# PX4FMUv1_6.net
KiCad netlist of a schematic drawn in EAGLE
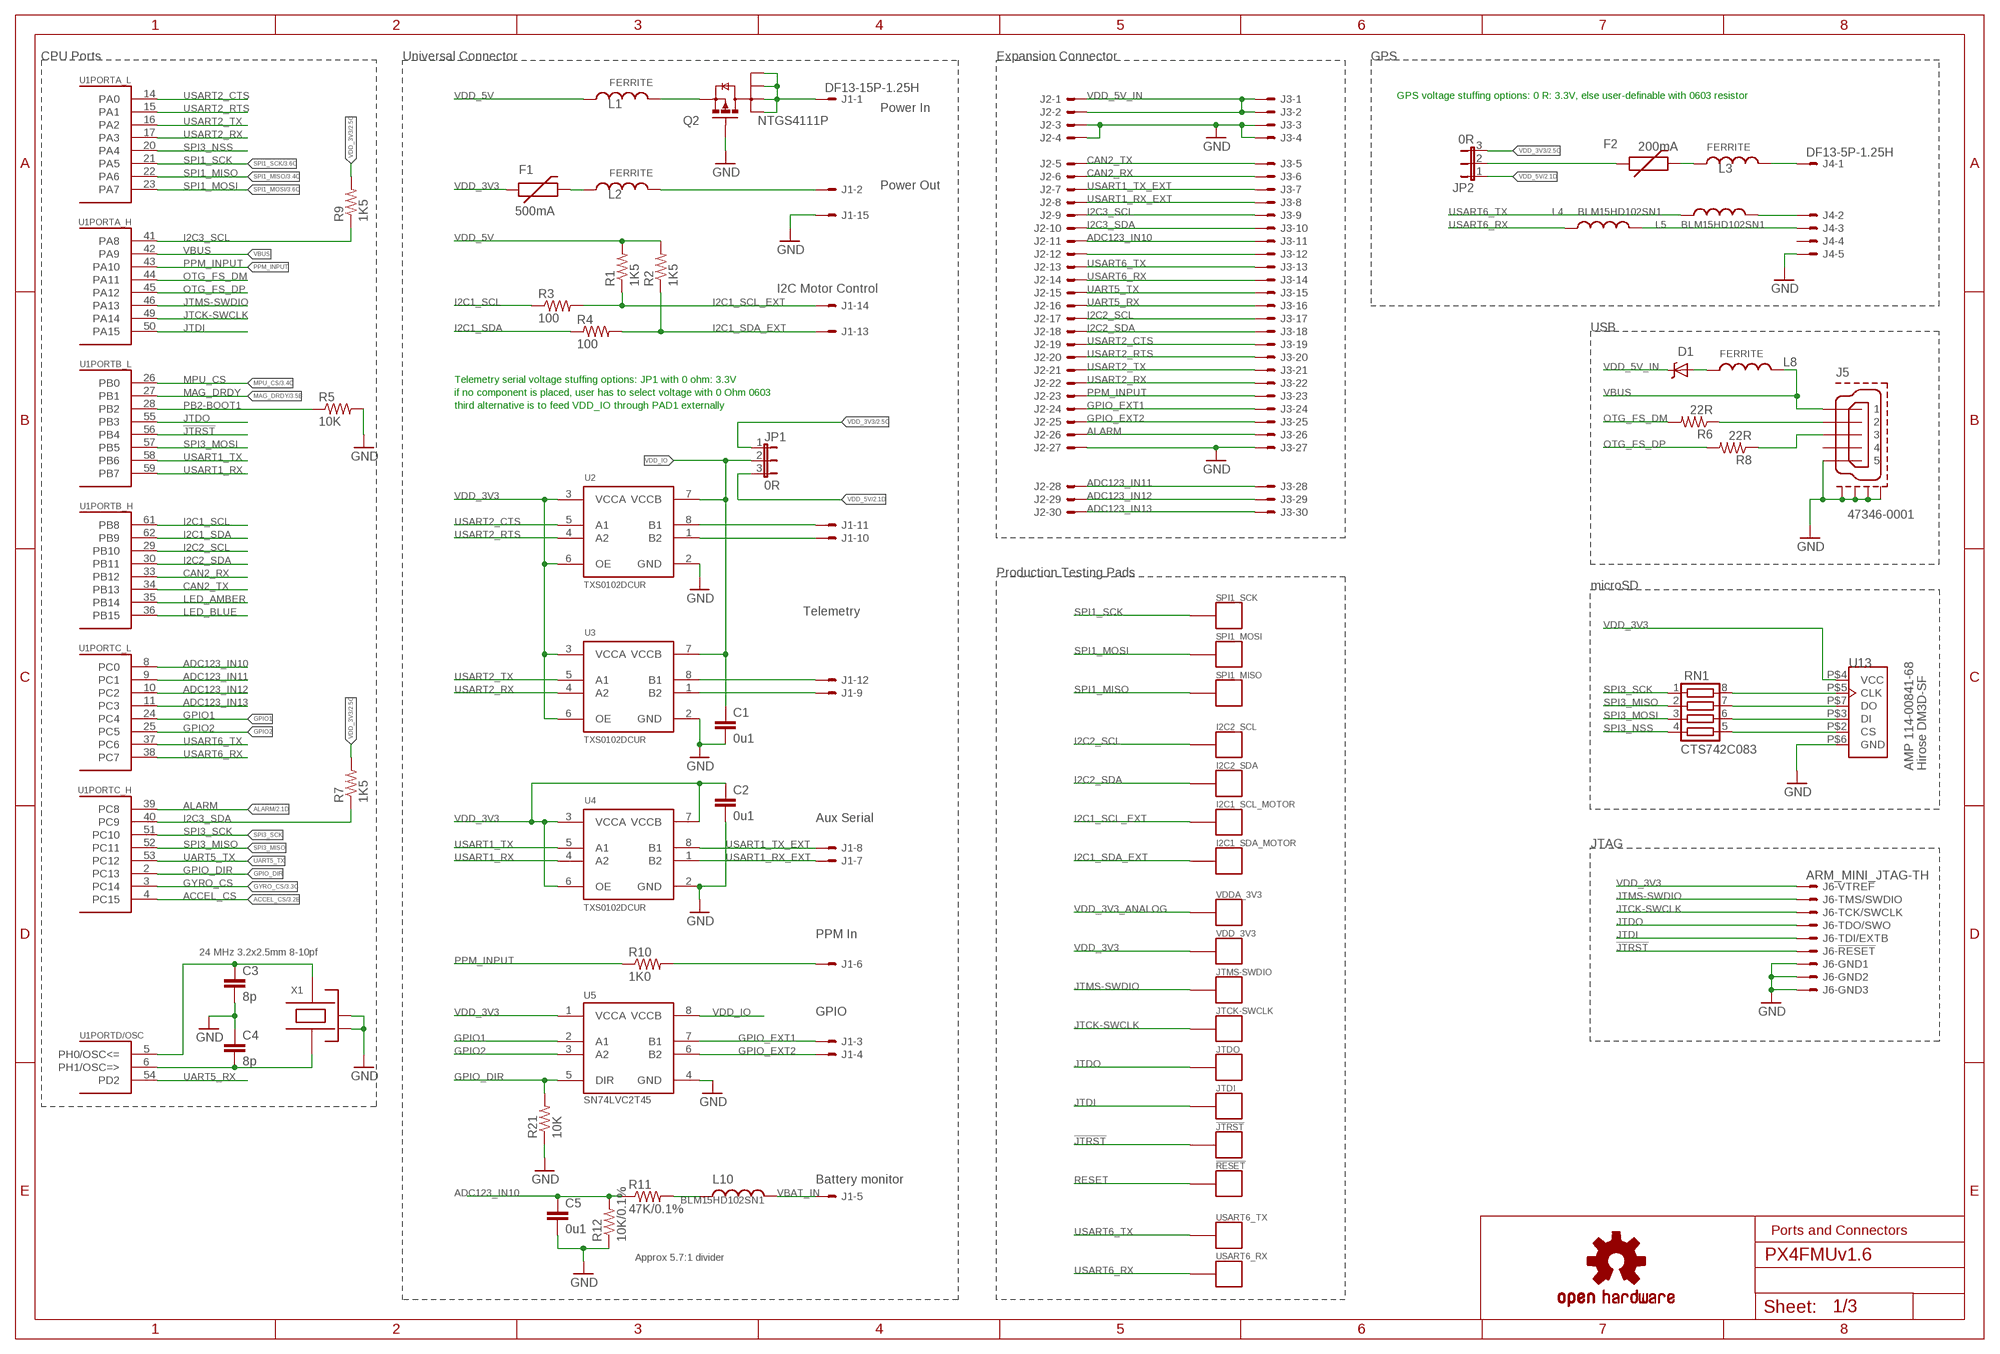
[diagram p0: schematic, sheet 1]
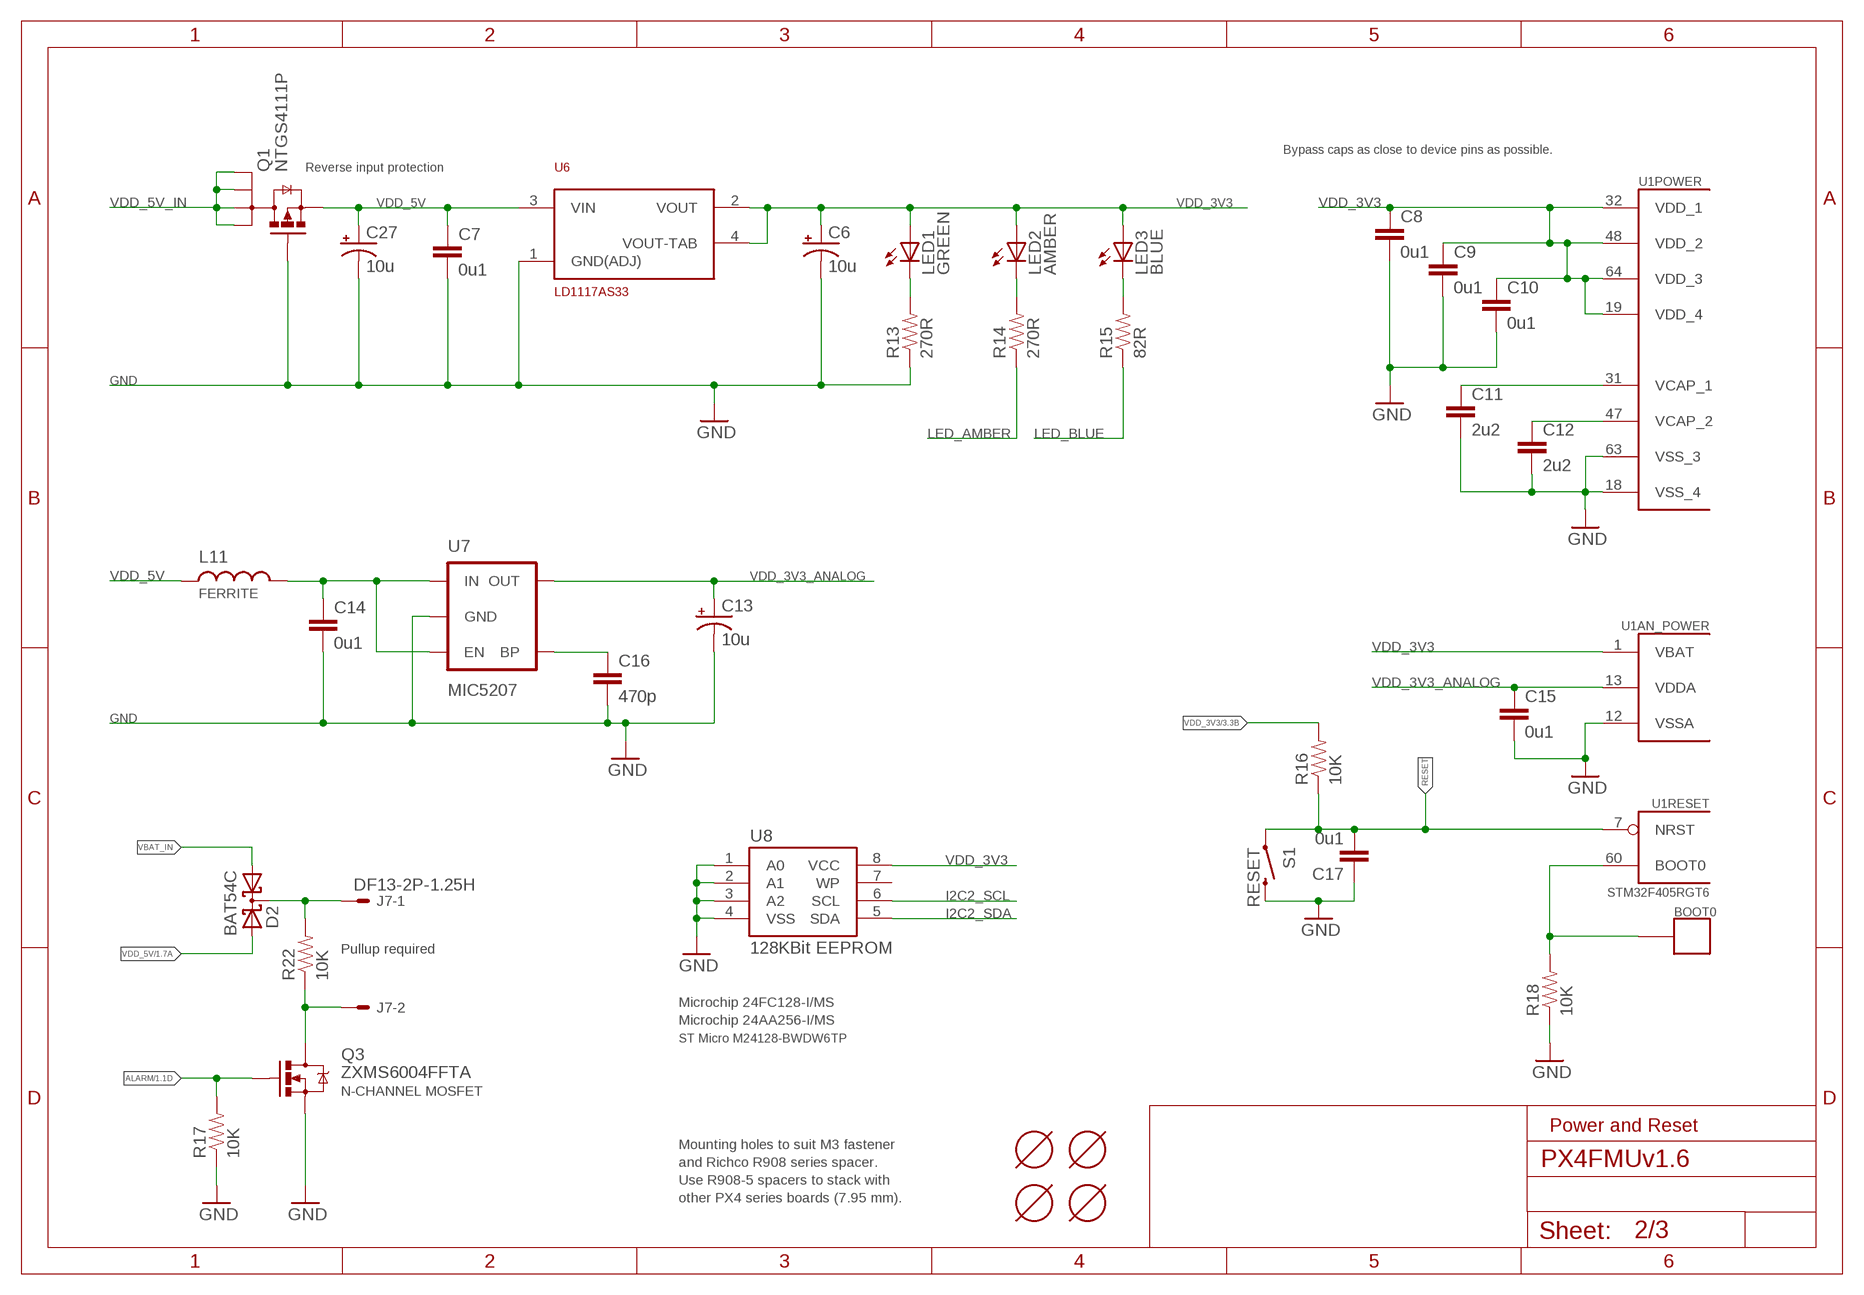
[diagram p1: schematic, sheet 2]
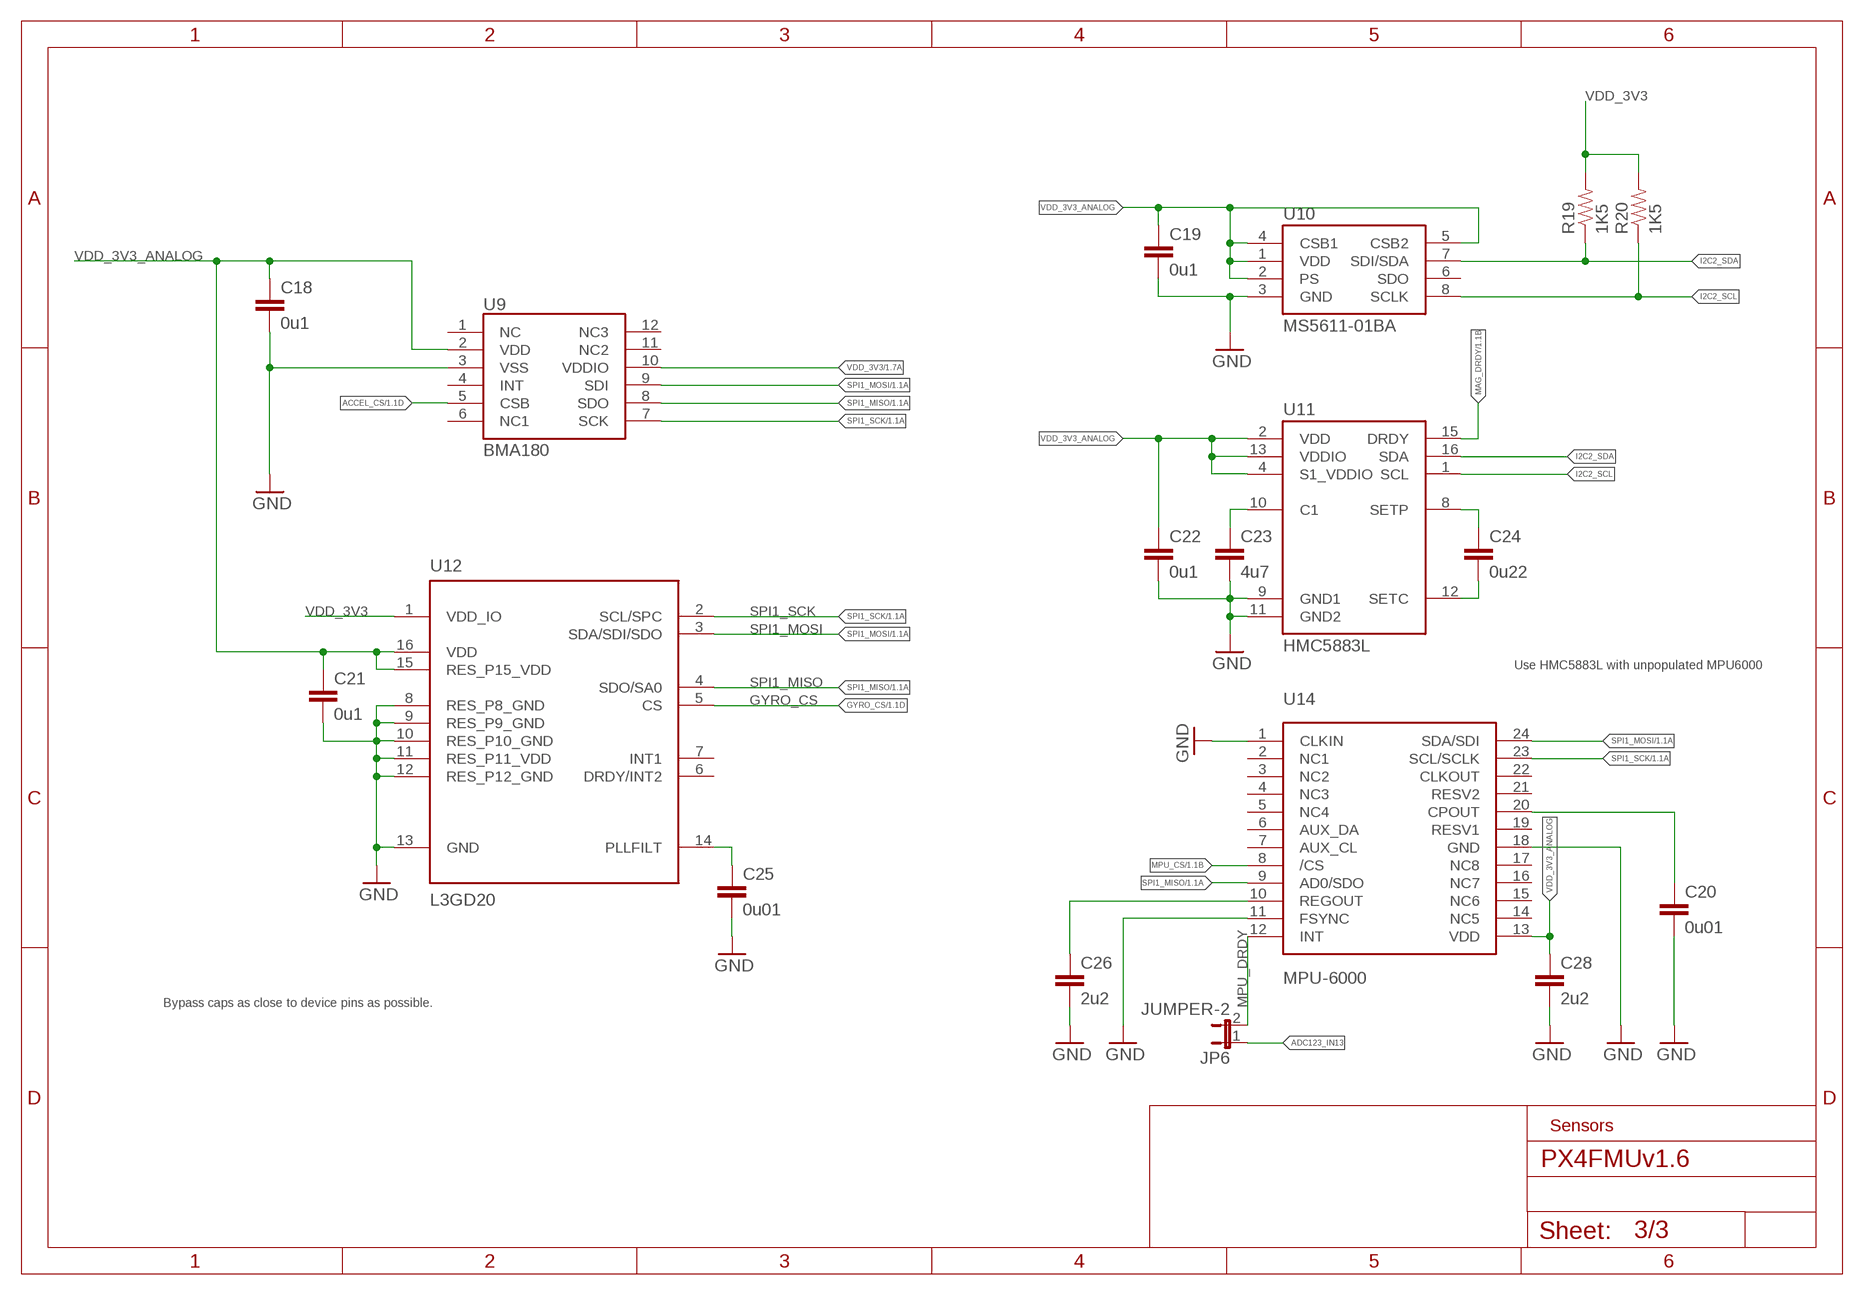
[diagram p2: schematic, sheet 3]

(export (version "E")
  (design (tool "Eeschema 10.0.6"))
  (components
    (comp (ref "!JTRST")
      (value "PAD.04")
      (footprint "eagle-import:PAD.04X.04")
      (libsource (lib "eagle-import") (part "PAD.04"))
    )
    (comp (ref "!RESET")
      (value "PAD.04")
      (footprint "eagle-import:PAD.04X.04")
      (libsource (lib "eagle-import") (part "PAD.04"))
    )
    (comp (ref "C1")
      (value "0u1")
      (footprint "eagle-import:0402-CAP")
      (fields (field (name "PARTNO") "CC0402ZRY5V7BB104"))
      (libsource (lib "eagle-import") (part "CAP0402-CAP"))
    )
    (comp (ref "C2")
      (value "0u1")
      (footprint "eagle-import:0402-CAP")
      (fields (field (name "PARTNO") "CC0402ZRY5V7BB104"))
      (libsource (lib "eagle-import") (part "CAP0402-CAP"))
    )
    (comp (ref "C3")
      (value "8p")
      (footprint "eagle-import:0402-CAP")
      (fields (field (name "PARTNO") "C1005C0G1H080C"))
      (libsource (lib "eagle-import") (part "CAP0402-CAP"))
    )
    (comp (ref "C4")
      (value "8p")
      (footprint "eagle-import:0402-CAP")
      (fields (field (name "PARTNO") "C1005C0G1H080C"))
      (libsource (lib "eagle-import") (part "CAP0402-CAP"))
    )
    (comp (ref "C5")
      (value "0u1")
      (footprint "eagle-import:0402-CAP")
      (fields (field (name "PARTNO") "CC0402ZRY5V7BB104"))
      (libsource (lib "eagle-import") (part "CAP0402-CAP"))
    )
    (comp (ref "D1")
      (value "MSS1P4-M3")
      (footprint "eagle-import:MICROSMP")
      (fields (field (name "PARTNO") "MSS1P4-M3/89A"))
      (libsource (lib "eagle-import") (part "DIODE-SCHOTTKY_MSMP"))
    )
    (comp (ref "F1")
      (value "500mA")
      (footprint "eagle-import:0402-PTC")
      (fields (field (name "PARTNO") "MF-FSMF050X-2"))
      (libsource (lib "eagle-import") (part "PTC0402"))
    )
    (comp (ref "F2")
      (value "200mA")
      (footprint "eagle-import:0402-PTC")
      (fields (field (name "PARTNO") "MF-FSMF020X-2"))
      (libsource (lib "eagle-import") (part "PTC0402"))
    )
    (comp (ref "I2C1_SCL_MOTOR")
      (value "PAD.03")
      (footprint "eagle-import:PAD.03X.03")
      (libsource (lib "eagle-import") (part "PAD.03"))
    )
    (comp (ref "I2C1_SDA_MOTOR")
      (value "PAD.03")
      (footprint "eagle-import:PAD.03X.03")
      (libsource (lib "eagle-import") (part "PAD.03"))
    )
    (comp (ref "I2C2_SCL")
      (value "PAD.03")
      (footprint "eagle-import:PAD.03X.03")
      (libsource (lib "eagle-import") (part "PAD.03"))
    )
    (comp (ref "I2C2_SDA")
      (value "PAD.04")
      (footprint "eagle-import:PAD.04X.04")
      (libsource (lib "eagle-import") (part "PAD.04"))
    )
    (comp (ref "J1")
      (value "DF13-15P-1.25H")
      (footprint "eagle-import:DF13A-15P-1.25H")
      (fields (field (name "PARTNO") "DF13A-15P-1.25H(20)"))
      (libsource (lib "eagle-import") (part "DF13-15P-1.25?H"))
    )
    (comp (ref "J2")
      (value "HEADER_2X15-REV")
      (footprint "eagle-import:HEADER_2MM_2X15_REVERSE")
      (fields (field (name "BOM") "EXCLUDE") (field (name "PARTNO") "953230-2000-AR-PR"))
      (libsource (lib "eagle-import") (part "HEADER_2X15-REV"))
    )
    (comp (ref "J3")
      (value "HEADER_2X15")
      (footprint "eagle-import:HEADER_2MM_2X15")
      (fields (field (name "PARTNO") "953230-2000-AR-PR"))
      (libsource (lib "eagle-import") (part "HEADER_2X15-SMD"))
    )
    (comp (ref "J4")
      (value "DF13-5P-1.25H")
      (footprint "eagle-import:DF13A-5P-1.25H")
      (fields (field (name "PARTNO") "DF13A-5P-1.25H(20)"))
      (libsource (lib "eagle-import") (part "DF13-5P-1.25?H"))
    )
    (comp (ref "J5")
      (value "47346-0001")
      (footprint "eagle-import:MOLEX-47346-0001")
      (libsource (lib "eagle-import") (part "MOLEX-47346-0001"))
    )
    (comp (ref "J6")
      (value "ARM_MINI_JTAG-TH")
      (footprint "eagle-import:FTSH-105-01-XXX-DV")
      (fields (field (name "PARTNO") "M50-3900542"))
      (libsource (lib "eagle-import") (part "ARM_MINI_JTAG-TH"))
    )
    (comp (ref "JP1")
      (value "0R")
      (footprint "eagle-import:SJ_3_0603_PASTE1&2")
      (fields (field (name "PARTNO") "RMCF0402ZT0R00"))
      (libsource (lib "eagle-import") (part "JUMPER-30603"))
    )
    (comp (ref "JP2")
      (value "0R")
      (footprint "eagle-import:SJ_3_0603_PASTE1&2")
      (fields (field (name "PARTNO") "RMCF0402ZT0R00"))
      (libsource (lib "eagle-import") (part "JUMPER-30603"))
    )
    (comp (ref "JTCK-SWCLK")
      (value "PAD.04")
      (footprint "eagle-import:PAD.04X.04")
      (libsource (lib "eagle-import") (part "PAD.04"))
    )
    (comp (ref "JTDI")
      (value "PAD.04")
      (footprint "eagle-import:PAD.04X.04")
      (libsource (lib "eagle-import") (part "PAD.04"))
    )
    (comp (ref "JTDO")
      (value "PAD.04")
      (footprint "eagle-import:PAD.04X.04")
      (libsource (lib "eagle-import") (part "PAD.04"))
    )
    (comp (ref "JTMS-SWDIO")
      (value "PAD.04")
      (footprint "eagle-import:PAD.04X.04")
      (libsource (lib "eagle-import") (part "PAD.04"))
    )
    (comp (ref "L1")
      (value "FERRITE")
      (footprint "eagle-import:0402-IND")
      (fields (field (name "PARTNO") "BKP1005HS121-T"))
      (libsource (lib "eagle-import") (part "INDUCTOR0402"))
    )
    (comp (ref "L2")
      (value "FERRITE")
      (footprint "eagle-import:0402-IND")
      (fields (field (name "PARTNO") "BKP1005HS121-T"))
      (libsource (lib "eagle-import") (part "INDUCTOR0402"))
    )
    (comp (ref "L3")
      (value "FERRITE")
      (footprint "eagle-import:0402-IND")
      (fields (field (name "PARTNO") "BKP1005HS121-T"))
      (libsource (lib "eagle-import") (part "INDUCTOR0402"))
    )
    (comp (ref "L4")
      (value "BLM15HD102SN1")
      (footprint "eagle-import:0402-IND")
      (libsource (lib "eagle-import") (part "INDUCTOR0402"))
    )
    (comp (ref "L5")
      (value "BLM15HD102SN1")
      (footprint "eagle-import:0402-IND")
      (libsource (lib "eagle-import") (part "INDUCTOR0402"))
    )
    (comp (ref "L8")
      (value "FERRITE")
      (footprint "eagle-import:0402-IND")
      (fields (field (name "PARTNO") "BKP1005HS121-T"))
      (libsource (lib "eagle-import") (part "INDUCTOR0402"))
    )
    (comp (ref "L10")
      (value "BLM15HD102SN1")
      (footprint "eagle-import:0402-IND")
      (libsource (lib "eagle-import") (part "INDUCTOR0402"))
    )
    (comp (ref "Q2")
      (value "NTGS4111P")
      (footprint "eagle-import:TSOP-6")
      (libsource (lib "eagle-import") (part "NTGS4111P"))
    )
    (comp (ref "R1")
      (value "1K5")
      (footprint "eagle-import:0402-RES")
      (fields (field (name "PARTNO") "RMCF0402JT1K50"))
      (libsource (lib "eagle-import") (part "RESISTOR0402-RES"))
    )
    (comp (ref "R2")
      (value "1K5")
      (footprint "eagle-import:0402-RES")
      (fields (field (name "PARTNO") "RMCF0402JT1K50"))
      (libsource (lib "eagle-import") (part "RESISTOR0402-RES"))
    )
    (comp (ref "R3")
      (value "100")
      (footprint "eagle-import:0402-RES")
      (fields (field (name "PARTNO") "RMCF0402JT100R"))
      (libsource (lib "eagle-import") (part "RESISTOR0402-RES"))
    )
    (comp (ref "R4")
      (value "100")
      (footprint "eagle-import:0402-RES")
      (fields (field (name "PARTNO") "RMCF0402JT100R"))
      (libsource (lib "eagle-import") (part "RESISTOR0402-RES"))
    )
    (comp (ref "R5")
      (value "10K")
      (footprint "eagle-import:0402-RES")
      (fields (field (name "PARTNO") "RMCF0402FT10K0"))
      (libsource (lib "eagle-import") (part "RESISTOR0402-RES"))
    )
    (comp (ref "R6")
      (value "22R")
      (footprint "eagle-import:0402-RES")
      (fields (field (name "PARTNO") "RMCF0402JT22R0"))
      (libsource (lib "eagle-import") (part "RESISTOR0402-RES"))
    )
    (comp (ref "R7")
      (value "1K5")
      (footprint "eagle-import:0402-RES")
      (fields (field (name "PARTNO") "RMCF0402JT1K50"))
      (libsource (lib "eagle-import") (part "RESISTOR0402-RES"))
    )
    (comp (ref "R8")
      (value "22R")
      (footprint "eagle-import:0402-RES")
      (fields (field (name "PARTNO") "RMCF0402JT22R0"))
      (libsource (lib "eagle-import") (part "RESISTOR0402-RES"))
    )
    (comp (ref "R9")
      (value "1K5")
      (footprint "eagle-import:0402-RES")
      (fields (field (name "PARTNO") "RMCF0402JT1K50"))
      (libsource (lib "eagle-import") (part "RESISTOR0402-RES"))
    )
    (comp (ref "R10")
      (value "1K0")
      (footprint "eagle-import:0402-RES")
      (fields (field (name "PARTNO") "RMCF0402JT1K00"))
      (libsource (lib "eagle-import") (part "RESISTOR0402-RES"))
    )
    (comp (ref "R11")
      (value "47K/0.1%")
      (footprint "eagle-import:0402-RES")
      (fields (field (name "PARTNO") "ERA-2AEB473X"))
      (libsource (lib "eagle-import") (part "RESISTOR0402-RES"))
    )
    (comp (ref "R12")
      (value "10K/0.1%")
      (footprint "eagle-import:0402-RES")
      (fields (field (name "PARTNO") "ERA-2AEB103X"))
      (libsource (lib "eagle-import") (part "RESISTOR0402-RES"))
    )
    (comp (ref "R21")
      (value "10K")
      (footprint "eagle-import:0402-RES")
      (fields (field (name "PARTNO") "RMCF0402FT10K0"))
      (libsource (lib "eagle-import") (part "RESISTOR0402-RES"))
    )
    (comp (ref "RN1")
      (value "CTS742C083")
      (footprint "eagle-import:CTS742C083")
      (fields (field (name "PARTNO") "TC164-JR-07100RL"))
      (libsource (lib "eagle-import") (part "CTS742C083"))
    )
    (comp (ref "SPI1_MISO")
      (value "PAD.04")
      (footprint "eagle-import:PAD.04X.04")
      (libsource (lib "eagle-import") (part "PAD.04"))
    )
    (comp (ref "SPI1_MOSI")
      (value "PAD.04")
      (footprint "eagle-import:PAD.04X.04")
      (libsource (lib "eagle-import") (part "PAD.04"))
    )
    (comp (ref "SPI1_SCK")
      (value "PAD.04")
      (footprint "eagle-import:PAD.04X.04")
      (libsource (lib "eagle-import") (part "PAD.04"))
    )
    (comp (ref "U$7")
      (value "OSHW-LOGOS")
      (footprint "eagle-import:OSHW-LOGO-S")
      (libsource (lib "eagle-import") (part "OSHW-LOGOS"))
    )
    (comp (ref "U1")
      (value "STM32F405RGT6")
      (footprint "eagle-import:TQFP64")
      (fields (field (name "PARTNO") "STM32F405RGT6"))
      (libsource (lib "eagle-import") (part "STM32F20X_TQFP64"))
    )
    (comp (ref "U2")
      (value "TXS0102DCUR")
      (footprint "eagle-import:TI-DCU")
      (libsource (lib "eagle-import") (part "TXS0102DCUR"))
    )
    (comp (ref "U3")
      (value "TXS0102DCUR")
      (footprint "eagle-import:TI-DCU")
      (libsource (lib "eagle-import") (part "TXS0102DCUR"))
    )
    (comp (ref "U4")
      (value "TXS0102DCUR")
      (footprint "eagle-import:TI-DCU")
      (libsource (lib "eagle-import") (part "TXS0102DCUR"))
    )
    (comp (ref "U5")
      (value "SN74LVC2T45")
      (footprint "eagle-import:TI-DCU")
      (libsource (lib "eagle-import") (part "SN74LVC2T45DCUR"))
    )
    (comp (ref "U13")
      (value "AMP 114-00841-68")
      (footprint "eagle-import:AMPHENOL_114-00841-68")
      (fields (field (name "PARTNO") "114-00841-68"))
      (libsource (lib "eagle-import") (part "SF-MICROSDAMP-114-00841-68"))
    )
    (comp (ref "USART6_RX")
      (value "PAD.04")
      (footprint "eagle-import:PAD.04X.04")
      (libsource (lib "eagle-import") (part "PAD.04"))
    )
    (comp (ref "USART6_TX")
      (value "PAD.04")
      (footprint "eagle-import:PAD.04X.04")
      (libsource (lib "eagle-import") (part "PAD.04"))
    )
    (comp (ref "VDDA_3V3")
      (value "PAD.04")
      (footprint "eagle-import:PAD.04X.04")
      (libsource (lib "eagle-import") (part "PAD.04"))
    )
    (comp (ref "VDD_3V3")
      (value "PAD.04")
      (footprint "eagle-import:PAD.04X.04")
      (libsource (lib "eagle-import") (part "PAD.04"))
    )
    (comp (ref "X1")
      (value "24 MHz 3.2x2.5mm 8-10pf")
      (footprint "eagle-import:OSCILLATOR-3.2X2.5")
      (fields (field (name "PARTNO") "NX3225SA-24.000000MHZ"))
      (libsource (lib "eagle-import") (part "OSCILLATOR-3.2X2.5"))
    )
    (comp (ref "BOOT0")
      (value "PAD.04")
      (footprint "eagle-import:PAD.04X.04")
      (libsource (lib "eagle-import") (part "PAD.04"))
    )
    (comp (ref "C6")
      (value "10u")
      (footprint "eagle-import:EIA3216")
      (fields (field (name "PARTNO") "F931A106MAA"))
      (libsource (lib "eagle-import") (part "CAP_POL1206"))
    )
    (comp (ref "C7")
      (value "0u1")
      (footprint "eagle-import:0402-CAP")
      (fields (field (name "PARTNO") "CC0402ZRY5V7BB104"))
      (libsource (lib "eagle-import") (part "CAP0402-CAP"))
    )
    (comp (ref "C8")
      (value "0u1")
      (footprint "eagle-import:0402-CAP")
      (fields (field (name "PARTNO") "CC0402ZRY5V7BB104"))
      (libsource (lib "eagle-import") (part "CAP0402-CAP"))
    )
    (comp (ref "C9")
      (value "0u1")
      (footprint "eagle-import:0402-CAP")
      (fields (field (name "PARTNO") "CC0402ZRY5V7BB104"))
      (libsource (lib "eagle-import") (part "CAP0402-CAP"))
    )
    (comp (ref "C10")
      (value "0u1")
      (footprint "eagle-import:0402-CAP")
      (fields (field (name "PARTNO") "CC0402ZRY5V7BB104"))
      (libsource (lib "eagle-import") (part "CAP0402-CAP"))
    )
    (comp (ref "C11")
      (value "2u2")
      (footprint "eagle-import:0402-CAP")
      (fields (field (name "PARTNO") "C1608Y5V1C225Z"))
      (libsource (lib "eagle-import") (part "CAP0402-CAP"))
    )
    (comp (ref "C12")
      (value "2u2")
      (footprint "eagle-import:0402-CAP")
      (fields (field (name "PARTNO") "C1608Y5V1C225Z"))
      (libsource (lib "eagle-import") (part "CAP0402-CAP"))
    )
    (comp (ref "C13")
      (value "10u")
      (footprint "eagle-import:EIA3216")
      (fields (field (name "PARTNO") "F931A106MAA"))
      (libsource (lib "eagle-import") (part "CAP_POL1206"))
    )
    (comp (ref "C14")
      (value "0u1")
      (footprint "eagle-import:0402-CAP")
      (fields (field (name "PARTNO") "CC0402ZRY5V7BB104"))
      (libsource (lib "eagle-import") (part "CAP0402-CAP"))
    )
    (comp (ref "C15")
      (value "0u1")
      (footprint "eagle-import:0402-CAP")
      (fields (field (name "PARTNO") "CC0402ZRY5V7BB104"))
      (libsource (lib "eagle-import") (part "CAP0402-CAP"))
    )
    (comp (ref "C16")
      (value "470p")
      (footprint "eagle-import:0402-CAP")
      (fields (field (name "PARTNO") "CC0402KRX7R9BB471"))
      (libsource (lib "eagle-import") (part "CAP0402-CAP"))
    )
    (comp (ref "C17")
      (value "0u1")
      (footprint "eagle-import:0402-CAP")
      (fields (field (name "PARTNO") "CC0402ZRY5V7BB104"))
      (libsource (lib "eagle-import") (part "CAP0402-CAP"))
    )
    (comp (ref "C27")
      (value "10u")
      (footprint "eagle-import:EIA3216")
      (fields (field (name "PARTNO") "F931A106MAA"))
      (libsource (lib "eagle-import") (part "CAP_POL1206"))
    )
    (comp (ref "D2")
      (value "BAT54C")
      (footprint "eagle-import:SOT23-3")
      (fields (field (name "PARTNO") "BAT54C-7-F"))
      (libsource (lib "eagle-import") (part "BAT54C"))
    )
    (comp (ref "J7")
      (value "DF13-2P-1.25H")
      (footprint "eagle-import:DF13A-2P-1.25H")
      (fields (field (name "PARTNO") "DF13-2P-1.25DSA"))
      (libsource (lib "eagle-import") (part "DF13-2P-1.25?H"))
    )
    (comp (ref "L11")
      (value "FERRITE")
      (footprint "eagle-import:0402-IND")
      (fields (field (name "PARTNO") "BKP1005HS121-T"))
      (libsource (lib "eagle-import") (part "INDUCTOR0402"))
    )
    (comp (ref "LED1")
      (value "GREEN")
      (footprint "eagle-import:LED-0603")
      (fields (field (name "PARTNO") "LNJ337W83RA"))
      (libsource (lib "eagle-import") (part "LED0603"))
    )
    (comp (ref "LED2")
      (value "AMBER")
      (footprint "eagle-import:LED-0603")
      (fields (field (name "PARTNO") "LNJ437W84RA"))
      (libsource (lib "eagle-import") (part "LED0603"))
    )
    (comp (ref "LED3")
      (value "BLUE")
      (footprint "eagle-import:LED-0603")
      (fields (field (name "PARTNO") "LNJ937W8CRA"))
      (libsource (lib "eagle-import") (part "LED0603"))
    )
    (comp (ref "Q1")
      (value "NTGS4111P")
      (footprint "eagle-import:TSOP-6")
      (libsource (lib "eagle-import") (part "NTGS4111P"))
    )
    (comp (ref "Q3")
      (value "ZXMS6004FFTA")
      (footprint "eagle-import:SOT23-3")
      (libsource (lib "eagle-import") (part "MOSFET-NCHANNELSMD"))
    )
    (comp (ref "R13")
      (value "270R")
      (footprint "eagle-import:0402-RES")
      (fields (field (name "PARTNO") "RC0402JR-07270RL"))
      (libsource (lib "eagle-import") (part "RESISTOR0402-RES"))
    )
    (comp (ref "R14")
      (value "270R")
      (footprint "eagle-import:0402-RES")
      (fields (field (name "PARTNO") "RC0402JR-07270RL"))
      (libsource (lib "eagle-import") (part "RESISTOR0402-RES"))
    )
    (comp (ref "R15")
      (value "82R")
      (footprint "eagle-import:0402-RES")
      (fields (field (name "PARTNO") "RC0402JR-0782RL"))
      (libsource (lib "eagle-import") (part "RESISTOR0402-RES"))
    )
    (comp (ref "R16")
      (value "10K")
      (footprint "eagle-import:0402-RES")
      (fields (field (name "PARTNO") "RMCF0402FT10K0"))
      (libsource (lib "eagle-import") (part "RESISTOR0402-RES"))
    )
    (comp (ref "R17")
      (value "10K")
      (footprint "eagle-import:0402-RES")
      (fields (field (name "PARTNO") "RMCF0402FT10K0"))
      (libsource (lib "eagle-import") (part "RESISTOR0402-RES"))
    )
    (comp (ref "R18")
      (value "10K")
      (footprint "eagle-import:0402-RES")
      (fields (field (name "PARTNO") "RMCF0402FT10K0"))
      (libsource (lib "eagle-import") (part "RESISTOR0402-RES"))
    )
    (comp (ref "R22")
      (value "10K")
      (footprint "eagle-import:0402-RES")
      (fields (field (name "PARTNO") "RMCF0402FT10K0"))
      (libsource (lib "eagle-import") (part "RESISTOR0402-RES"))
    )
    (comp (ref "S1")
      (value "RESET")
      (footprint "eagle-import:EVQP7J01K")
      (fields (field (name "PARTNO") "EVQP7J01K"))
      (libsource (lib "eagle-import") (part "SWITCH-MOMENTARY-2"))
    )
    (comp (ref "U$1")
      (value "MOUNT-HOLE3.1MM")
      (footprint "eagle-import:MOUNT-HOLE3.1")
      (libsource (lib "eagle-import") (part "MOUNT-HOLE3.1MM"))
    )
    (comp (ref "U$2")
      (value "MOUNT-HOLE3.1MM")
      (footprint "eagle-import:MOUNT-HOLE3.1")
      (libsource (lib "eagle-import") (part "MOUNT-HOLE3.1MM"))
    )
    (comp (ref "U$3")
      (value "MOUNT-HOLE3.1MM")
      (footprint "eagle-import:MOUNT-HOLE3.1")
      (libsource (lib "eagle-import") (part "MOUNT-HOLE3.1MM"))
    )
    (comp (ref "U$4")
      (value "MOUNT-HOLE3.1MM")
      (footprint "eagle-import:MOUNT-HOLE3.1")
      (libsource (lib "eagle-import") (part "MOUNT-HOLE3.1MM"))
    )
    (comp (ref "U6")
      (value "LD1117AS33")
      (footprint "eagle-import:SOT-223")
      (libsource (lib "eagle-import") (part "LD1117AS33"))
    )
    (comp (ref "U7")
      (value "MIC5207")
      (footprint "eagle-import:SOT23-5")
      (fields (field (name "PARTNO") "MIC5207-3.3YM5"))
      (libsource (lib "eagle-import") (part "V_REG_LDOSMD"))
    )
    (comp (ref "U8")
      (value "128KBit EEPROM")
      (footprint "eagle-import:MSOP-8")
      (fields (field (name "PARTNO") "24FC128-I/MS"))
      (libsource (lib "eagle-import") (part "EEPROM-I2CMSOP"))
    )
    (comp (ref "C18")
      (value "0u1")
      (footprint "eagle-import:0402-CAP")
      (fields (field (name "PARTNO") "CC0402ZRY5V7BB104"))
      (libsource (lib "eagle-import") (part "CAP0402-CAP"))
    )
    (comp (ref "C19")
      (value "0u1")
      (footprint "eagle-import:0402-CAP")
      (fields (field (name "PARTNO") "CC0402ZRY5V7BB104"))
      (libsource (lib "eagle-import") (part "CAP0402-CAP"))
    )
    (comp (ref "C20")
      (value "0u01")
      (footprint "eagle-import:0402-CAP")
      (fields (field (name "PARTNO") "CC0402KRX7R7BB103"))
      (libsource (lib "eagle-import") (part "CAP0402-CAP"))
    )
    (comp (ref "C21")
      (value "0u1")
      (footprint "eagle-import:0402-CAP")
      (fields (field (name "PARTNO") "CC0402ZRY5V7BB104"))
      (libsource (lib "eagle-import") (part "CAP0402-CAP"))
    )
    (comp (ref "C22")
      (value "0u1")
      (footprint "eagle-import:0402-CAP")
      (fields (field (name "PARTNO") "CC0402ZRY5V7BB104"))
      (libsource (lib "eagle-import") (part "CAP0402-CAP"))
    )
    (comp (ref "C23")
      (value "4u7")
      (footprint "eagle-import:0402-CAP")
      (fields (field (name "PARTNO") "C1608Y5V0J475Z"))
      (libsource (lib "eagle-import") (part "CAP0402-CAP"))
    )
    (comp (ref "C24")
      (value "0u22")
      (footprint "eagle-import:0402-CAP")
      (fields (field (name "PARTNO") "C1005Y5V1C224Z"))
      (libsource (lib "eagle-import") (part "CAP0402-CAP"))
    )
    (comp (ref "C25")
      (value "0u01")
      (footprint "eagle-import:0402-CAP")
      (fields (field (name "PARTNO") "CC0402KRX7R7BB103"))
      (libsource (lib "eagle-import") (part "CAP0402-CAP"))
    )
    (comp (ref "C26")
      (value "2u2")
      (footprint "eagle-import:0402-CAP")
      (fields (field (name "PARTNO") "C1608Y5V1C225Z"))
      (libsource (lib "eagle-import") (part "CAP0402-CAP"))
    )
    (comp (ref "C28")
      (value "2u2")
      (footprint "eagle-import:0402-CAP")
      (fields (field (name "PARTNO") "C1608Y5V1C225Z"))
      (libsource (lib "eagle-import") (part "CAP0402-CAP"))
    )
    (comp (ref "JP6")
      (value "JUMPER-2")
      (footprint "eagle-import:SJ_2")
      (libsource (lib "eagle-import") (part "JUMPER-2"))
    )
    (comp (ref "R19")
      (value "1K5")
      (footprint "eagle-import:0402-RES")
      (fields (field (name "PARTNO") "RMCF0402JT1K50"))
      (libsource (lib "eagle-import") (part "RESISTOR0402-RES"))
    )
    (comp (ref "R20")
      (value "1K5")
      (footprint "eagle-import:0402-RES")
      (fields (field (name "PARTNO") "RMCF0402JT1K50"))
      (libsource (lib "eagle-import") (part "RESISTOR0402-RES"))
    )
    (comp (ref "U9")
      (value "BMA180")
      (footprint "eagle-import:LGA12")
      (libsource (lib "eagle-import") (part "BMA180"))
    )
    (comp (ref "U10")
      (value "MS5611-01BA")
      (footprint "eagle-import:MS5611-01BA")
      (libsource (lib "eagle-import") (part "MS5611-01BA"))
    )
    (comp (ref "U11")
      (value "HMC5883L")
      (footprint "eagle-import:HMC5883L-MAN")
      (libsource (lib "eagle-import") (part "HMC5883L"))
    )
    (comp (ref "U12")
      (value "L3GD20")
      (footprint "eagle-import:L3G4200DH-MAN")
      (libsource (lib "eagle-import") (part "L3G4200DH-LL"))
    )
    (comp (ref "U14")
      (value "MPU-6000")
      (footprint "eagle-import:QFN-24")
      (libsource (lib "eagle-import") (part "MPU-6000"))
    )
  )
  (nets
    (net (code "1") (name "ACCEL_CS") (class "Default")
      (node (ref "U1") (pin "4") (pinfunction "PC15_4") (pintype "bidirectional"))
      (node (ref "U9") (pin "5") (pinfunction "CSB_5") (pintype "bidirectional"))
    )
    (net (code "2") (name "ADC123_IN10") (class "Default")
      (node (ref "C5") (pin "1") (pinfunction "1_1") (pintype "passive"))
      (node (ref "J2") (pin "11") (pinfunction "S_11") (pintype "passive"))
      (node (ref "J3") (pin "11") (pinfunction "S_11") (pintype "passive"))
      (node (ref "R11") (pin "1") (pinfunction "1_1") (pintype "passive"))
      (node (ref "R12") (pin "2") (pinfunction "2_2") (pintype "passive"))
      (node (ref "U1") (pin "8") (pinfunction "PC0_8") (pintype "bidirectional"))
    )
    (net (code "3") (name "ADC123_IN11") (class "Default")
      (node (ref "J2") (pin "28") (pinfunction "S_28") (pintype "passive"))
      (node (ref "J3") (pin "28") (pinfunction "S_28") (pintype "passive"))
      (node (ref "U1") (pin "9") (pinfunction "PC1_9") (pintype "bidirectional"))
    )
    (net (code "4") (name "ADC123_IN12") (class "Default")
      (node (ref "J2") (pin "29") (pinfunction "S_29") (pintype "passive"))
      (node (ref "J3") (pin "29") (pinfunction "S_29") (pintype "passive"))
      (node (ref "U1") (pin "10") (pinfunction "PC2_10") (pintype "bidirectional"))
    )
    (net (code "5") (name "ADC123_IN13") (class "Default")
      (node (ref "J2") (pin "30") (pinfunction "S_30") (pintype "passive"))
      (node (ref "J3") (pin "30") (pinfunction "S_30") (pintype "passive"))
      (node (ref "JP6") (pin "1") (pinfunction "1_1") (pintype "passive"))
      (node (ref "U1") (pin "11") (pinfunction "PC3_11") (pintype "bidirectional"))
    )
    (net (code "6") (name "ALARM") (class "Default")
      (node (ref "J2") (pin "26") (pinfunction "S_26") (pintype "passive"))
      (node (ref "J3") (pin "26") (pinfunction "S_26") (pintype "passive"))
      (node (ref "Q3") (pin "1") (pinfunction "G_1") (pintype "passive"))
      (node (ref "R17") (pin "2") (pinfunction "2_2") (pintype "passive"))
      (node (ref "U1") (pin "39") (pinfunction "PC8_39") (pintype "bidirectional"))
    )
    (net (code "7") (name "CAN2_RX") (class "Default")
      (node (ref "J2") (pin "6") (pinfunction "S_6") (pintype "passive"))
      (node (ref "J3") (pin "6") (pinfunction "S_6") (pintype "passive"))
      (node (ref "U1") (pin "33") (pinfunction "PB12_33") (pintype "bidirectional"))
    )
    (net (code "8") (name "CAN2_TX") (class "Default")
      (node (ref "J2") (pin "5") (pinfunction "S_5") (pintype "passive"))
      (node (ref "J3") (pin "5") (pinfunction "S_5") (pintype "passive"))
      (node (ref "U1") (pin "34") (pinfunction "PB13_34") (pintype "bidirectional"))
    )
    (net (code "9") (name "GND") (class "Default")
      (node (ref "C1") (pin "2") (pinfunction "2_2") (pintype "passive"))
      (node (ref "C10") (pin "2") (pinfunction "2_2") (pintype "passive"))
      (node (ref "C11") (pin "2") (pinfunction "2_2") (pintype "passive"))
      (node (ref "C12") (pin "2") (pinfunction "2_2") (pintype "passive"))
      (node (ref "C13") (pin "C") (pinfunction "-_C") (pintype "passive"))
      (node (ref "C14") (pin "2") (pinfunction "2_2") (pintype "passive"))
      (node (ref "C15") (pin "2") (pinfunction "2_2") (pintype "passive"))
      (node (ref "C16") (pin "2") (pinfunction "2_2") (pintype "passive"))
      (node (ref "C17") (pin "1") (pinfunction "1_1") (pintype "passive"))
      (node (ref "C18") (pin "2") (pinfunction "2_2") (pintype "passive"))
      (node (ref "C19") (pin "2") (pinfunction "2_2") (pintype "passive"))
      (node (ref "C2") (pin "2") (pinfunction "2_2") (pintype "passive"))
      (node (ref "C20") (pin "2") (pinfunction "2_2") (pintype "passive"))
      (node (ref "C21") (pin "2") (pinfunction "2_2") (pintype "passive"))
      (node (ref "C22") (pin "2") (pinfunction "2_2") (pintype "passive"))
      (node (ref "C23") (pin "2") (pinfunction "2_2") (pintype "passive"))
      (node (ref "C25") (pin "2") (pinfunction "2_2") (pintype "passive"))
      (node (ref "C26") (pin "2") (pinfunction "2_2") (pintype "passive"))
      (node (ref "C27") (pin "C") (pinfunction "-_C") (pintype "passive"))
      (node (ref "C28") (pin "2") (pinfunction "2_2") (pintype "passive"))
      (node (ref "C3") (pin "2") (pinfunction "2_2") (pintype "passive"))
      (node (ref "C4") (pin "1") (pinfunction "1_1") (pintype "passive"))
      (node (ref "C5") (pin "2") (pinfunction "2_2") (pintype "passive"))
      (node (ref "C6") (pin "C") (pinfunction "-_C") (pintype "passive"))
      (node (ref "C7") (pin "2") (pinfunction "2_2") (pintype "passive"))
      (node (ref "C8") (pin "2") (pinfunction "2_2") (pintype "passive"))
      (node (ref "C9") (pin "2") (pinfunction "2_2") (pintype "passive"))
      (node (ref "J1") (pin "15") (pinfunction "S_15") (pintype "passive"))
      (node (ref "J2") (pin "27") (pinfunction "S_27") (pintype "passive"))
      (node (ref "J2") (pin "3") (pinfunction "S_3") (pintype "passive"))
      (node (ref "J2") (pin "4") (pinfunction "S_4") (pintype "passive"))
      (node (ref "J3") (pin "27") (pinfunction "S_27") (pintype "passive"))
      (node (ref "J3") (pin "3") (pinfunction "S_3") (pintype "passive"))
      (node (ref "J3") (pin "4") (pinfunction "S_4") (pintype "passive"))
      (node (ref "J4") (pin "5") (pinfunction "S_5") (pintype "passive"))
      (node (ref "J5") (pin "GND") (pinfunction "5_GND") (pintype "power_in"))
      (node (ref "J5") (pin "GND1") (pinfunction "GND1_GND1") (pintype "bidirectional"))
      (node (ref "J5") (pin "GND2") (pinfunction "GND2_GND2") (pintype "bidirectional"))
      (node (ref "J5") (pin "GND3") (pinfunction "GND3_GND3") (pintype "bidirectional"))
      (node (ref "J5") (pin "GND4") (pinfunction "GND4_GND4") (pintype "bidirectional"))
      (node (ref "J6") (pin "3") (pinfunction "S_3") (pintype "passive"))
      (node (ref "J6") (pin "5") (pinfunction "S_5") (pintype "passive"))
      (node (ref "J6") (pin "9") (pinfunction "S_9") (pintype "passive"))
      (node (ref "Q1") (pin "3") (pinfunction "G_3") (pintype "passive"))
      (node (ref "Q2") (pin "3") (pinfunction "G_3") (pintype "passive"))
      (node (ref "Q3") (pin "2") (pinfunction "S_2") (pintype "passive"))
      (node (ref "R12") (pin "1") (pinfunction "1_1") (pintype "passive"))
      (node (ref "R13") (pin "1") (pinfunction "1_1") (pintype "passive"))
      (node (ref "R17") (pin "1") (pinfunction "1_1") (pintype "passive"))
      (node (ref "R18") (pin "1") (pinfunction "1_1") (pintype "passive"))
      (node (ref "R21") (pin "1") (pinfunction "1_1") (pintype "passive"))
      (node (ref "R5") (pin "2") (pinfunction "2_2") (pintype "passive"))
      (node (ref "S1") (pin "B3") (pinfunction "2_B3") (pintype "passive"))
      (node (ref "U1") (pin "12") (pinfunction "VSSA_12") (pintype "power_in"))
      (node (ref "U1") (pin "18") (pinfunction "VSS_4_18") (pintype "power_in"))
      (node (ref "U1") (pin "63") (pinfunction "VSS_3_63") (pintype "power_in"))
      (node (ref "U10") (pin "3") (pinfunction "GND_3") (pintype "bidirectional"))
      (node (ref "U11") (pin "11") (pinfunction "GND2_11") (pintype "bidirectional"))
      (node (ref "U11") (pin "9") (pinfunction "GND1_9") (pintype "bidirectional"))
      (node (ref "U12") (pin "10") (pinfunction "RES_P10_GND_10") (pintype "bidirectional"))
      (node (ref "U12") (pin "11") (pinfunction "RES_P11_VDD_11") (pintype "bidirectional"))
      (node (ref "U12") (pin "12") (pinfunction "RES_P12_GND_12") (pintype "bidirectional"))
      (node (ref "U12") (pin "13") (pinfunction "GND_13") (pintype "bidirectional"))
      (node (ref "U12") (pin "8") (pinfunction "RES_P8_GND_8") (pintype "bidirectional"))
      (node (ref "U12") (pin "9") (pinfunction "RES_P9_GND_9") (pintype "bidirectional"))
      (node (ref "U13") (pin "P$6") (pinfunction "GND_P$6") (pintype "power_in"))
      (node (ref "U14") (pin "1") (pinfunction "CLKIN_1") (pintype "bidirectional"))
      (node (ref "U14") (pin "11") (pinfunction "FSYNC_11") (pintype "bidirectional"))
      (node (ref "U14") (pin "18") (pinfunction "GND_18") (pintype "bidirectional"))
      (node (ref "U2") (pin "2") (pinfunction "GND_2") (pintype "power_in"))
      (node (ref "U3") (pin "2") (pinfunction "GND_2") (pintype "power_in"))
      (node (ref "U4") (pin "2") (pinfunction "GND_2") (pintype "power_in"))
      (node (ref "U5") (pin "4") (pinfunction "GND_4") (pintype "power_in"))
      (node (ref "U6") (pin "1") (pinfunction "GND(ADJ)_1") (pintype "bidirectional"))
      (node (ref "U7") (pin "2") (pinfunction "GND_2") (pintype "input"))
      (node (ref "U8") (pin "1") (pinfunction "A0_1") (pintype "bidirectional"))
      (node (ref "U8") (pin "2") (pinfunction "A1_2") (pintype "bidirectional"))
      (node (ref "U8") (pin "3") (pinfunction "A2_3") (pintype "bidirectional"))
      (node (ref "U8") (pin "4") (pinfunction "VSS_4") (pintype "power_in"))
      (node (ref "U9") (pin "3") (pinfunction "VSS_3") (pintype "bidirectional"))
      (node (ref "X1") (pin "2") (pinfunction "NC_2_2") (pintype "power_in"))
      (node (ref "X1") (pin "4") (pinfunction "NC_4_4") (pintype "power_in"))
    )
    (net (code "10") (name "GPIO1") (class "Default")
      (node (ref "U1") (pin "24") (pinfunction "PC4_24") (pintype "bidirectional"))
      (node (ref "U5") (pin "2") (pinfunction "A1_2") (pintype "bidirectional"))
    )
    (net (code "11") (name "GPIO2") (class "Default")
      (node (ref "U1") (pin "25") (pinfunction "PC5_25") (pintype "bidirectional"))
      (node (ref "U5") (pin "3") (pinfunction "A2_3") (pintype "bidirectional"))
    )
    (net (code "12") (name "GPIO_DIR") (class "Default")
      (node (ref "R21") (pin "2") (pinfunction "2_2") (pintype "passive"))
      (node (ref "U1") (pin "2") (pinfunction "PC13_2") (pintype "bidirectional"))
      (node (ref "U5") (pin "5") (pinfunction "DIR_5") (pintype "input"))
    )
    (net (code "13") (name "GPIO_EXT1") (class "Default")
      (node (ref "J1") (pin "3") (pinfunction "S_3") (pintype "passive"))
      (node (ref "J2") (pin "24") (pinfunction "S_24") (pintype "passive"))
      (node (ref "J3") (pin "24") (pinfunction "S_24") (pintype "passive"))
      (node (ref "U5") (pin "7") (pinfunction "B1_7") (pintype "bidirectional"))
    )
    (net (code "14") (name "GPIO_EXT2") (class "Default")
      (node (ref "J1") (pin "4") (pinfunction "S_4") (pintype "passive"))
      (node (ref "J2") (pin "25") (pinfunction "S_25") (pintype "passive"))
      (node (ref "J3") (pin "25") (pinfunction "S_25") (pintype "passive"))
      (node (ref "U5") (pin "6") (pinfunction "B2_6") (pintype "bidirectional"))
    )
    (net (code "15") (name "GYRO_CS") (class "Default")
      (node (ref "U1") (pin "3") (pinfunction "PC14_3") (pintype "bidirectional"))
      (node (ref "U12") (pin "5") (pinfunction "CS_5") (pintype "input"))
    )
    (net (code "16") (name "I2C1_SCL") (class "Default")
      (node (ref "R3") (pin "1") (pinfunction "1_1") (pintype "passive"))
      (node (ref "U1") (pin "61") (pinfunction "PB8_61") (pintype "bidirectional"))
    )
    (net (code "17") (name "I2C1_SCL_EXT") (class "Default")
      (node (ref "I2C1_SCL_MOTOR") (pin "P$1") (pinfunction "P$1_P$1") (pintype "passive"))
      (node (ref "J1") (pin "14") (pinfunction "S_14") (pintype "passive"))
      (node (ref "R1") (pin "1") (pinfunction "1_1") (pintype "passive"))
      (node (ref "R3") (pin "2") (pinfunction "2_2") (pintype "passive"))
    )
    (net (code "18") (name "I2C1_SDA") (class "Default")
      (node (ref "R4") (pin "1") (pinfunction "1_1") (pintype "passive"))
      (node (ref "U1") (pin "62") (pinfunction "PB9_62") (pintype "bidirectional"))
    )
    (net (code "19") (name "I2C1_SDA_EXT") (class "Default")
      (node (ref "I2C1_SDA_MOTOR") (pin "P$1") (pinfunction "P$1_P$1") (pintype "passive"))
      (node (ref "J1") (pin "13") (pinfunction "S_13") (pintype "passive"))
      (node (ref "R2") (pin "1") (pinfunction "1_1") (pintype "passive"))
      (node (ref "R4") (pin "2") (pinfunction "2_2") (pintype "passive"))
    )
    (net (code "20") (name "I2C2_SCL") (class "Default")
      (node (ref "I2C2_SCL") (pin "P$1") (pinfunction "P$1_P$1") (pintype "passive"))
      (node (ref "J2") (pin "17") (pinfunction "S_17") (pintype "passive"))
      (node (ref "J3") (pin "17") (pinfunction "S_17") (pintype "passive"))
      (node (ref "R20") (pin "1") (pinfunction "1_1") (pintype "passive"))
      (node (ref "U1") (pin "29") (pinfunction "PB10_29") (pintype "bidirectional"))
      (node (ref "U10") (pin "8") (pinfunction "SCLK_8") (pintype "bidirectional"))
      (node (ref "U11") (pin "1") (pinfunction "SCL_1") (pintype "bidirectional"))
      (node (ref "U8") (pin "6") (pinfunction "SCL_6") (pintype "bidirectional"))
    )
    (net (code "21") (name "I2C2_SDA") (class "Default")
      (node (ref "I2C2_SDA") (pin "P$1") (pinfunction "P$1_P$1") (pintype "passive"))
      (node (ref "J2") (pin "18") (pinfunction "S_18") (pintype "passive"))
      (node (ref "J3") (pin "18") (pinfunction "S_18") (pintype "passive"))
      (node (ref "R19") (pin "1") (pinfunction "1_1") (pintype "passive"))
      (node (ref "U1") (pin "30") (pinfunction "PB11_30") (pintype "bidirectional"))
      (node (ref "U10") (pin "7") (pinfunction "SDI/SDA_7") (pintype "bidirectional"))
      (node (ref "U11") (pin "16") (pinfunction "SDA_16") (pintype "bidirectional"))
      (node (ref "U8") (pin "5") (pinfunction "SDA_5") (pintype "bidirectional"))
    )
    (net (code "22") (name "I2C3_SCL") (class "Default")
      (node (ref "J2") (pin "9") (pinfunction "S_9") (pintype "passive"))
      (node (ref "J3") (pin "9") (pinfunction "S_9") (pintype "passive"))
      (node (ref "R9") (pin "1") (pinfunction "1_1") (pintype "passive"))
      (node (ref "U1") (pin "41") (pinfunction "PA8_41") (pintype "bidirectional"))
    )
    (net (code "23") (name "I2C3_SDA") (class "Default")
      (node (ref "J2") (pin "10") (pinfunction "S_10") (pintype "passive"))
      (node (ref "J3") (pin "10") (pinfunction "S_10") (pintype "passive"))
      (node (ref "R7") (pin "1") (pinfunction "1_1") (pintype "passive"))
      (node (ref "U1") (pin "40") (pinfunction "PC9_40") (pintype "bidirectional"))
    )
    (net (code "24") (name "JTCK-SWCLK") (class "Default")
      (node (ref "J6") (pin "4") (pinfunction "S_4") (pintype "passive"))
      (node (ref "JTCK-SWCLK") (pin "P$1") (pinfunction "P$1_P$1") (pintype "passive"))
      (node (ref "U1") (pin "49") (pinfunction "PA14_49") (pintype "bidirectional"))
    )
    (net (code "25") (name "JTDI") (class "Default")
      (node (ref "J6") (pin "8") (pinfunction "S_8") (pintype "passive"))
      (node (ref "JTDI") (pin "P$1") (pinfunction "P$1_P$1") (pintype "passive"))
      (node (ref "U1") (pin "50") (pinfunction "PA15_50") (pintype "bidirectional"))
    )
    (net (code "26") (name "JTDO") (class "Default")
      (node (ref "J6") (pin "6") (pinfunction "S_6") (pintype "passive"))
      (node (ref "JTDO") (pin "P$1") (pinfunction "P$1_P$1") (pintype "passive"))
      (node (ref "U1") (pin "55") (pinfunction "PB3_55") (pintype "bidirectional"))
    )
    (net (code "27") (name "JTMS-SWDIO") (class "Default")
      (node (ref "J6") (pin "2") (pinfunction "S_2") (pintype "passive"))
      (node (ref "JTMS-SWDIO") (pin "P$1") (pinfunction "P$1_P$1") (pintype "passive"))
      (node (ref "U1") (pin "46") (pinfunction "PA13_46") (pintype "bidirectional"))
    )
    (net (code "28") (name "LED_AMBER") (class "Default")
      (node (ref "R14") (pin "1") (pinfunction "1_1") (pintype "passive"))
      (node (ref "U1") (pin "35") (pinfunction "PB14_35") (pintype "bidirectional"))
    )
    (net (code "29") (name "LED_BLUE") (class "Default")
      (node (ref "R15") (pin "1") (pinfunction "1_1") (pintype "passive"))
      (node (ref "U1") (pin "36") (pinfunction "PB15_36") (pintype "bidirectional"))
    )
    (net (code "30") (name "MAG_DRDY") (class "Default")
      (node (ref "U1") (pin "27") (pinfunction "PB1_27") (pintype "bidirectional"))
      (node (ref "U11") (pin "15") (pinfunction "DRDY_15") (pintype "bidirectional"))
    )
    (net (code "31") (name "MPU_CS") (class "Default")
      (node (ref "U1") (pin "26") (pinfunction "PB0_26") (pintype "bidirectional"))
      (node (ref "U14") (pin "8") (pinfunction "/CS_8") (pintype "bidirectional"))
    )
    (net (code "32") (name "Net-(D1-A)") (class "Default")
      (node (ref "D1") (pin "ANODE") (pinfunction "A_ANODE") (pintype "passive"))
      (node (ref "L8") (pin "1") (pinfunction "1_1") (pintype "passive"))
    )
    (net (code "33") (name "Net-(D2-CC)") (class "Default")
      (node (ref "D2") (pin "3") (pinfunction "CC_3") (pintype "passive"))
      (node (ref "J7") (pin "1") (pinfunction "S_1") (pintype "passive"))
      (node (ref "R22") (pin "2") (pinfunction "2_2") (pintype "passive"))
    )
    (net (code "34") (name "Net-(F1-Pad2)") (class "Default")
      (node (ref "F1") (pin "2") (pinfunction "2_2") (pintype "bidirectional"))
      (node (ref "L2") (pin "1") (pinfunction "1_1") (pintype "passive"))
    )
    (net (code "35") (name "Net-(F2-Pad1)") (class "Default")
      (node (ref "F2") (pin "1") (pinfunction "1_1") (pintype "bidirectional"))
      (node (ref "JP2") (pin "2") (pinfunction "2_2") (pintype "passive"))
    )
    (net (code "36") (name "Net-(F2-Pad2)") (class "Default")
      (node (ref "F2") (pin "2") (pinfunction "2_2") (pintype "bidirectional"))
      (node (ref "L3") (pin "1") (pinfunction "1_1") (pintype "passive"))
    )
    (net (code "37") (name "Net-(J1A-S)") (class "Default")
      (node (ref "J1") (pin "1") (pinfunction "S_1") (pintype "passive"))
      (node (ref "Q2") (pin "1") (pinfunction "D_1") (pintype "passive"))
      (node (ref "Q2") (pin "2") (pinfunction "D1_2") (pintype "passive"))
      (node (ref "Q2") (pin "5") (pinfunction "D2_5") (pintype "passive"))
      (node (ref "Q2") (pin "6") (pinfunction "D3_6") (pintype "passive"))
    )
    (net (code "38") (name "Net-(J1B-S)") (class "Default")
      (node (ref "J1") (pin "10") (pinfunction "S_10") (pintype "passive"))
      (node (ref "U2") (pin "1") (pinfunction "B2_1") (pintype "bidirectional"))
    )
    (net (code "39") (name "Net-(J1C-S)") (class "Default")
      (node (ref "J1") (pin "11") (pinfunction "S_11") (pintype "passive"))
      (node (ref "U2") (pin "8") (pinfunction "B1_8") (pintype "bidirectional"))
    )
    (net (code "40") (name "Net-(J1D-S)") (class "Default")
      (node (ref "J1") (pin "12") (pinfunction "S_12") (pintype "passive"))
      (node (ref "U3") (pin "8") (pinfunction "B1_8") (pintype "bidirectional"))
    )
    (net (code "41") (name "Net-(J1H-S)") (class "Default")
      (node (ref "J1") (pin "2") (pinfunction "S_2") (pintype "passive"))
      (node (ref "L2") (pin "2") (pinfunction "2_2") (pintype "passive"))
    )
    (net (code "42") (name "Net-(J1L-S)") (class "Default")
      (node (ref "J1") (pin "6") (pinfunction "S_6") (pintype "passive"))
      (node (ref "R10") (pin "2") (pinfunction "2_2") (pintype "passive"))
    )
    (net (code "43") (name "Net-(J1O-S)") (class "Default")
      (node (ref "J1") (pin "9") (pinfunction "S_9") (pintype "passive"))
      (node (ref "U3") (pin "1") (pinfunction "B2_1") (pintype "bidirectional"))
    )
    (net (code "44") (name "Net-(J2D-S)") (class "Default")
      (node (ref "J2") (pin "12") (pinfunction "S_12") (pintype "passive"))
      (node (ref "J3") (pin "12") (pinfunction "S_12") (pintype "passive"))
    )
    (net (code "45") (name "Net-(J4A-S)") (class "Default")
      (node (ref "J4") (pin "1") (pinfunction "S_1") (pintype "passive"))
      (node (ref "L3") (pin "2") (pinfunction "2_2") (pintype "passive"))
    )
    (net (code "46") (name "Net-(J4B-S)") (class "Default")
      (node (ref "J4") (pin "2") (pinfunction "S_2") (pintype "passive"))
      (node (ref "L5") (pin "2") (pinfunction "2_2") (pintype "passive"))
    )
    (net (code "47") (name "Net-(J4C-S)") (class "Default")
      (node (ref "J4") (pin "3") (pinfunction "S_3") (pintype "passive"))
      (node (ref "L4") (pin "2") (pinfunction "2_2") (pintype "passive"))
    )
    (net (code "48") (name "Net-(J5-2)") (class "Default")
      (node (ref "J5") (pin "D-") (pinfunction "2_D-") (pintype "bidirectional"))
      (node (ref "R6") (pin "1") (pinfunction "1_1") (pintype "passive"))
    )
    (net (code "49") (name "Net-(J5-3)") (class "Default")
      (node (ref "J5") (pin "D+") (pinfunction "3_D+") (pintype "bidirectional"))
      (node (ref "R8") (pin "1") (pinfunction "1_1") (pintype "passive"))
    )
    (net (code "50") (name "Net-(J7B-S)") (class "Default")
      (node (ref "J7") (pin "2") (pinfunction "S_2") (pintype "passive"))
      (node (ref "Q3") (pin "3") (pinfunction "D_3") (pintype "passive"))
      (node (ref "R22") (pin "1") (pinfunction "1_1") (pintype "passive"))
    )
    (net (code "51") (name "Net-(L10-Pad1)") (class "Default")
      (node (ref "L10") (pin "1") (pinfunction "1_1") (pintype "passive"))
      (node (ref "R11") (pin "2") (pinfunction "2_2") (pintype "passive"))
    )
    (net (code "52") (name "Net-(LED1-PadC)") (class "Default")
      (node (ref "LED1") (pin "C") (pinfunction "C_C") (pintype "passive"))
      (node (ref "R13") (pin "2") (pinfunction "2_2") (pintype "passive"))
    )
    (net (code "53") (name "Net-(LED2-PadC)") (class "Default")
      (node (ref "LED2") (pin "C") (pinfunction "C_C") (pintype "passive"))
      (node (ref "R14") (pin "2") (pinfunction "2_2") (pintype "passive"))
    )
    (net (code "54") (name "Net-(LED3-PadC)") (class "Default")
      (node (ref "LED3") (pin "C") (pinfunction "C_C") (pintype "passive"))
      (node (ref "R15") (pin "2") (pinfunction "2_2") (pintype "passive"))
    )
    (net (code "55") (name "Net-(Q2-S)") (class "Default")
      (node (ref "L1") (pin "2") (pinfunction "2_2") (pintype "passive"))
      (node (ref "Q2") (pin "4") (pinfunction "S_4") (pintype "passive"))
    )
    (net (code "56") (name "Net-(U1H-PH0{slash}OSC<=)") (class "Default")
      (node (ref "C3") (pin "1") (pinfunction "1_1") (pintype "passive"))
      (node (ref "U1") (pin "5") (pinfunction "PH0/OSC<=_5") (pintype "bidirectional"))
      (node (ref "X1") (pin "3") (pinfunction "3_3") (pintype "bidirectional"))
    )
    (net (code "57") (name "Net-(U1H-PH1{slash}OSC=>)") (class "Default")
      (node (ref "C4") (pin "2") (pinfunction "2_2") (pintype "passive"))
      (node (ref "U1") (pin "6") (pinfunction "PH1/OSC=>_6") (pintype "bidirectional"))
      (node (ref "X1") (pin "1") (pinfunction "1_1") (pintype "bidirectional"))
    )
    (net (code "58") (name "Net-(U1I-VCAP_1)") (class "Default")
      (node (ref "C11") (pin "1") (pinfunction "1_1") (pintype "passive"))
      (node (ref "U1") (pin "31") (pinfunction "VCAP_1_31") (pintype "power_in"))
    )
    (net (code "59") (name "Net-(U1I-VCAP_2)") (class "Default")
      (node (ref "C12") (pin "1") (pinfunction "1_1") (pintype "passive"))
      (node (ref "U1") (pin "47") (pinfunction "VCAP_2_47") (pintype "power_in"))
    )
    (net (code "60") (name "Net-(U1J-BOOT0)") (class "Default")
      (node (ref "BOOT0") (pin "P$1") (pinfunction "P$1_P$1") (pintype "passive"))
      (node (ref "R18") (pin "2") (pinfunction "2_2") (pintype "passive"))
      (node (ref "U1") (pin "60") (pinfunction "BOOT0_60") (pintype "input"))
    )
    (net (code "61") (name "Net-(U7-BP)") (class "Default")
      (node (ref "C16") (pin "1") (pinfunction "1_1") (pintype "passive"))
      (node (ref "U7") (pin "4") (pinfunction "BP_4") (pintype "input"))
    )
    (net (code "62") (name "Net-(U7-EN)") (class "Default")
      (node (ref "C14") (pin "1") (pinfunction "1_1") (pintype "passive"))
      (node (ref "L11") (pin "2") (pinfunction "2_2") (pintype "passive"))
      (node (ref "U7") (pin "1") (pinfunction "IN_1") (pintype "input"))
      (node (ref "U7") (pin "3") (pinfunction "EN_3") (pintype "input"))
    )
    (net (code "63") (name "Net-(U11-C1)") (class "Default")
      (node (ref "C23") (pin "1") (pinfunction "1_1") (pintype "passive"))
      (node (ref "U11") (pin "10") (pinfunction "C1_10") (pintype "bidirectional"))
    )
    (net (code "64") (name "Net-(U11-SETC)") (class "Default")
      (node (ref "C24") (pin "2") (pinfunction "2_2") (pintype "passive"))
      (node (ref "U11") (pin "12") (pinfunction "SETC_12") (pintype "bidirectional"))
    )
    (net (code "65") (name "Net-(U11-SETP)") (class "Default")
      (node (ref "C24") (pin "1") (pinfunction "1_1") (pintype "passive"))
      (node (ref "U11") (pin "8") (pinfunction "SETP_8") (pintype "bidirectional"))
    )
    (net (code "66") (name "Net-(U12-PLLFILT)") (class "Default")
      (node (ref "C25") (pin "1") (pinfunction "1_1") (pintype "passive"))
      (node (ref "U12") (pin "14") (pinfunction "PLLFILT_14") (pintype "bidirectional"))
    )
    (net (code "67") (name "Net-(U13-CLK)") (class "Default")
      (node (ref "RN1") (pin "8") (pinfunction "8_8") (pintype "passive"))
      (node (ref "U13") (pin "P$5") (pinfunction "CLK_P$5") (pintype "bidirectional"))
    )
    (net (code "68") (name "Net-(U13-CS)") (class "Default")
      (node (ref "RN1") (pin "5") (pinfunction "5_5") (pintype "passive"))
      (node (ref "U13") (pin "P$2") (pinfunction "CS_P$2") (pintype "bidirectional"))
    )
    (net (code "69") (name "Net-(U13-DI)") (class "Default")
      (node (ref "RN1") (pin "6") (pinfunction "6_6") (pintype "passive"))
      (node (ref "U13") (pin "P$3") (pinfunction "DI_P$3") (pintype "bidirectional"))
    )
    (net (code "70") (name "Net-(U13-DO)") (class "Default")
      (node (ref "RN1") (pin "7") (pinfunction "7_7") (pintype "passive"))
      (node (ref "U13") (pin "P$7") (pinfunction "DO_P$7") (pintype "bidirectional"))
    )
    (net (code "71") (name "Net-(U14-CPOUT)") (class "Default")
      (node (ref "C20") (pin "1") (pinfunction "1_1") (pintype "passive"))
      (node (ref "U14") (pin "20") (pinfunction "CPOUT_20") (pintype "bidirectional"))
    )
    (net (code "72") (name "Net-(U14-INT)") (class "Default")
      (node (ref "JP6") (pin "2") (pinfunction "2_2") (pintype "passive"))
      (node (ref "U14") (pin "12") (pinfunction "INT_12") (pintype "bidirectional"))
    )
    (net (code "73") (name "Net-(U14-REGOUT)") (class "Default")
      (node (ref "C26") (pin "1") (pinfunction "1_1") (pintype "passive"))
      (node (ref "U14") (pin "10") (pinfunction "REGOUT_10") (pintype "bidirectional"))
    )
    (net (code "74") (name "OTG_FS_DM") (class "Default")
      (node (ref "R6") (pin "2") (pinfunction "2_2") (pintype "passive"))
      (node (ref "U1") (pin "44") (pinfunction "PA11_44") (pintype "bidirectional"))
    )
    (net (code "75") (name "OTG_FS_DP") (class "Default")
      (node (ref "R8") (pin "2") (pinfunction "2_2") (pintype "passive"))
      (node (ref "U1") (pin "45") (pinfunction "PA12_45") (pintype "bidirectional"))
    )
    (net (code "76") (name "PB2-BOOT1") (class "Default")
      (node (ref "R5") (pin "1") (pinfunction "1_1") (pintype "passive"))
      (node (ref "U1") (pin "28") (pinfunction "PB2_28") (pintype "bidirectional"))
    )
    (net (code "77") (name "PPM_INPUT") (class "Default")
      (node (ref "J2") (pin "23") (pinfunction "S_23") (pintype "passive"))
      (node (ref "J3") (pin "23") (pinfunction "S_23") (pintype "passive"))
      (node (ref "R10") (pin "1") (pinfunction "1_1") (pintype "passive"))
      (node (ref "U1") (pin "43") (pinfunction "PA10_43") (pintype "bidirectional"))
    )
    (net (code "78") (name "RESET") (class "Default")
      (node (ref "!RESET") (pin "P$1") (pinfunction "P$1_P$1") (pintype "passive"))
      (node (ref "C17") (pin "2") (pinfunction "2_2") (pintype "passive"))
      (node (ref "R16") (pin "1") (pinfunction "1_1") (pintype "passive"))
      (node (ref "S1") (pin "A1") (pinfunction "1_A1") (pintype "passive"))
      (node (ref "U1") (pin "7") (pinfunction "NRST_7") (pintype "input"))
    )
    (net (code "79") (name "SPI1_MISO") (class "Default")
      (node (ref "SPI1_MISO") (pin "P$1") (pinfunction "P$1_P$1") (pintype "passive"))
      (node (ref "U1") (pin "22") (pinfunction "PA6_22") (pintype "bidirectional"))
      (node (ref "U12") (pin "4") (pinfunction "SDO/SA0_4") (pintype "bidirectional"))
      (node (ref "U14") (pin "9") (pinfunction "AD0/SDO_9") (pintype "bidirectional"))
      (node (ref "U9") (pin "8") (pinfunction "SDO_8") (pintype "bidirectional"))
    )
    (net (code "80") (name "SPI1_MOSI") (class "Default")
      (node (ref "SPI1_MOSI") (pin "P$1") (pinfunction "P$1_P$1") (pintype "passive"))
      (node (ref "U1") (pin "23") (pinfunction "PA7_23") (pintype "bidirectional"))
      (node (ref "U12") (pin "3") (pinfunction "SDA/SDI/SDO_3") (pintype "bidirectional"))
      (node (ref "U14") (pin "24") (pinfunction "SDA/SDI_24") (pintype "bidirectional"))
      (node (ref "U9") (pin "9") (pinfunction "SDI_9") (pintype "bidirectional"))
    )
    (net (code "81") (name "SPI1_SCK") (class "Default")
      (node (ref "SPI1_SCK") (pin "P$1") (pinfunction "P$1_P$1") (pintype "passive"))
      (node (ref "U1") (pin "21") (pinfunction "PA5_21") (pintype "bidirectional"))
      (node (ref "U12") (pin "2") (pinfunction "SCL/SPC_2") (pintype "input"))
      (node (ref "U14") (pin "23") (pinfunction "SCL/SCLK_23") (pintype "bidirectional"))
      (node (ref "U9") (pin "7") (pinfunction "SCK_7") (pintype "bidirectional"))
    )
    (net (code "82") (name "SPI3_MISO") (class "Default")
      (node (ref "RN1") (pin "2") (pinfunction "2_2") (pintype "passive"))
      (node (ref "U1") (pin "52") (pinfunction "PC11_52") (pintype "bidirectional"))
    )
    (net (code "83") (name "SPI3_MOSI") (class "Default")
      (node (ref "RN1") (pin "3") (pinfunction "3_3") (pintype "passive"))
      (node (ref "U1") (pin "57") (pinfunction "PB5_57") (pintype "bidirectional"))
    )
    (net (code "84") (name "SPI3_NSS") (class "Default")
      (node (ref "RN1") (pin "4") (pinfunction "4_4") (pintype "passive"))
      (node (ref "U1") (pin "20") (pinfunction "PA4_20") (pintype "bidirectional"))
    )
    (net (code "85") (name "SPI3_SCK") (class "Default")
      (node (ref "RN1") (pin "1") (pinfunction "1_1") (pintype "passive"))
      (node (ref "U1") (pin "51") (pinfunction "PC10_51") (pintype "bidirectional"))
    )
    (net (code "86") (name "UART5_RX") (class "Default")
      (node (ref "J2") (pin "16") (pinfunction "S_16") (pintype "passive"))
      (node (ref "J3") (pin "16") (pinfunction "S_16") (pintype "passive"))
      (node (ref "U1") (pin "54") (pinfunction "PD2_54") (pintype "bidirectional"))
    )
    (net (code "87") (name "UART5_TX") (class "Default")
      (node (ref "J2") (pin "15") (pinfunction "S_15") (pintype "passive"))
      (node (ref "J3") (pin "15") (pinfunction "S_15") (pintype "passive"))
      (node (ref "U1") (pin "53") (pinfunction "PC12_53") (pintype "bidirectional"))
    )
    (net (code "88") (name "USART1_RX") (class "Default")
      (node (ref "U1") (pin "59") (pinfunction "PB7_59") (pintype "bidirectional"))
      (node (ref "U4") (pin "4") (pinfunction "A2_4") (pintype "bidirectional"))
    )
    (net (code "89") (name "USART1_RX_EXT") (class "Default")
      (node (ref "J1") (pin "7") (pinfunction "S_7") (pintype "passive"))
      (node (ref "J2") (pin "8") (pinfunction "S_8") (pintype "passive"))
      (node (ref "J3") (pin "8") (pinfunction "S_8") (pintype "passive"))
      (node (ref "U4") (pin "1") (pinfunction "B2_1") (pintype "bidirectional"))
    )
    (net (code "90") (name "USART1_TX") (class "Default")
      (node (ref "U1") (pin "58") (pinfunction "PB6_58") (pintype "bidirectional"))
      (node (ref "U4") (pin "5") (pinfunction "A1_5") (pintype "bidirectional"))
    )
    (net (code "91") (name "USART1_TX_EXT") (class "Default")
      (node (ref "J1") (pin "8") (pinfunction "S_8") (pintype "passive"))
      (node (ref "J2") (pin "7") (pinfunction "S_7") (pintype "passive"))
      (node (ref "J3") (pin "7") (pinfunction "S_7") (pintype "passive"))
      (node (ref "U4") (pin "8") (pinfunction "B1_8") (pintype "bidirectional"))
    )
    (net (code "92") (name "USART2_CTS") (class "Default")
      (node (ref "J2") (pin "19") (pinfunction "S_19") (pintype "passive"))
      (node (ref "J3") (pin "19") (pinfunction "S_19") (pintype "passive"))
      (node (ref "U1") (pin "14") (pinfunction "PA0_14") (pintype "bidirectional"))
      (node (ref "U2") (pin "5") (pinfunction "A1_5") (pintype "bidirectional"))
    )
    (net (code "93") (name "USART2_RTS") (class "Default")
      (node (ref "J2") (pin "20") (pinfunction "S_20") (pintype "passive"))
      (node (ref "J3") (pin "20") (pinfunction "S_20") (pintype "passive"))
      (node (ref "U1") (pin "15") (pinfunction "PA1_15") (pintype "bidirectional"))
      (node (ref "U2") (pin "4") (pinfunction "A2_4") (pintype "bidirectional"))
    )
    (net (code "94") (name "USART2_RX") (class "Default")
      (node (ref "J2") (pin "22") (pinfunction "S_22") (pintype "passive"))
      (node (ref "J3") (pin "22") (pinfunction "S_22") (pintype "passive"))
      (node (ref "U1") (pin "17") (pinfunction "PA3_17") (pintype "bidirectional"))
      (node (ref "U3") (pin "4") (pinfunction "A2_4") (pintype "bidirectional"))
    )
    (net (code "95") (name "USART2_TX") (class "Default")
      (node (ref "J2") (pin "21") (pinfunction "S_21") (pintype "passive"))
      (node (ref "J3") (pin "21") (pinfunction "S_21") (pintype "passive"))
      (node (ref "U1") (pin "16") (pinfunction "PA2_16") (pintype "bidirectional"))
      (node (ref "U3") (pin "5") (pinfunction "A1_5") (pintype "bidirectional"))
    )
    (net (code "96") (name "USART6_RX") (class "Default")
      (node (ref "J2") (pin "14") (pinfunction "S_14") (pintype "passive"))
      (node (ref "J3") (pin "14") (pinfunction "S_14") (pintype "passive"))
      (node (ref "L4") (pin "1") (pinfunction "1_1") (pintype "passive"))
      (node (ref "U1") (pin "38") (pinfunction "PC7_38") (pintype "bidirectional"))
      (node (ref "USART6_RX") (pin "P$1") (pinfunction "P$1_P$1") (pintype "passive"))
    )
    (net (code "97") (name "USART6_TX") (class "Default")
      (node (ref "J2") (pin "13") (pinfunction "S_13") (pintype "passive"))
      (node (ref "J3") (pin "13") (pinfunction "S_13") (pintype "passive"))
      (node (ref "L5") (pin "1") (pinfunction "1_1") (pintype "passive"))
      (node (ref "U1") (pin "37") (pinfunction "PC6_37") (pintype "bidirectional"))
      (node (ref "USART6_TX") (pin "P$1") (pinfunction "P$1_P$1") (pintype "passive"))
    )
    (net (code "98") (name "VBAT_IN") (class "Default")
      (node (ref "D2") (pin "1") (pinfunction "A1_1") (pintype "passive"))
      (node (ref "J1") (pin "5") (pinfunction "S_5") (pintype "passive"))
      (node (ref "L10") (pin "2") (pinfunction "2_2") (pintype "passive"))
    )
    (net (code "99") (name "VBUS") (class "Default")
      (node (ref "J5") (pin "VBUS") (pinfunction "1_VBUS") (pintype "power_in"))
      (node (ref "L8") (pin "2") (pinfunction "2_2") (pintype "passive"))
      (node (ref "U1") (pin "42") (pinfunction "PA9_42") (pintype "bidirectional"))
    )
    (net (code "100") (name "VDD_3V3") (class "Default")
      (node (ref "C10") (pin "1") (pinfunction "1_1") (pintype "passive"))
      (node (ref "C2") (pin "1") (pinfunction "1_1") (pintype "passive"))
      (node (ref "C6") (pin "A") (pinfunction "+_A") (pintype "passive"))
      (node (ref "C8") (pin "1") (pinfunction "1_1") (pintype "passive"))
      (node (ref "C9") (pin "1") (pinfunction "1_1") (pintype "passive"))
      (node (ref "F1") (pin "1") (pinfunction "1_1") (pintype "bidirectional"))
      (node (ref "J6") (pin "1") (pinfunction "S_1") (pintype "passive"))
      (node (ref "JP1") (pin "1") (pinfunction "1_1") (pintype "passive"))
      (node (ref "JP2") (pin "3") (pinfunction "3_3") (pintype "passive"))
      (node (ref "LED1") (pin "A") (pinfunction "A_A") (pintype "passive"))
      (node (ref "LED2") (pin "A") (pinfunction "A_A") (pintype "passive"))
      (node (ref "LED3") (pin "A") (pinfunction "A_A") (pintype "passive"))
      (node (ref "R16") (pin "2") (pinfunction "2_2") (pintype "passive"))
      (node (ref "R19") (pin "2") (pinfunction "2_2") (pintype "passive"))
      (node (ref "R20") (pin "2") (pinfunction "2_2") (pintype "passive"))
      (node (ref "R7") (pin "2") (pinfunction "2_2") (pintype "passive"))
      (node (ref "R9") (pin "2") (pinfunction "2_2") (pintype "passive"))
      (node (ref "U1") (pin "1") (pinfunction "VBAT_1") (pintype "power_in"))
      (node (ref "U1") (pin "19") (pinfunction "VDD_4_19") (pintype "power_in"))
      (node (ref "U1") (pin "32") (pinfunction "VDD_1_32") (pintype "power_in"))
      (node (ref "U1") (pin "48") (pinfunction "VDD_2_48") (pintype "power_in"))
      (node (ref "U1") (pin "64") (pinfunction "VDD_3_64") (pintype "power_in"))
      (node (ref "U12") (pin "1") (pinfunction "VDD_IO_1") (pintype "bidirectional"))
      (node (ref "U13") (pin "P$4") (pinfunction "VCC_P$4") (pintype "passive"))
      (node (ref "U2") (pin "3") (pinfunction "VCCA_3") (pintype "input"))
      (node (ref "U2") (pin "6") (pinfunction "OE_6") (pintype "input"))
      (node (ref "U3") (pin "3") (pinfunction "VCCA_3") (pintype "input"))
      (node (ref "U3") (pin "6") (pinfunction "OE_6") (pintype "input"))
      (node (ref "U4") (pin "3") (pinfunction "VCCA_3") (pintype "input"))
      (node (ref "U4") (pin "6") (pinfunction "OE_6") (pintype "input"))
      (node (ref "U4") (pin "7") (pinfunction "VCCB_7") (pintype "input"))
      (node (ref "U5") (pin "1") (pinfunction "VCCA_1") (pintype "passive"))
      (node (ref "U6") (pin "2") (pinfunction "VOUT_2") (pintype "bidirectional"))
      (node (ref "U6") (pin "4") (pinfunction "VOUT-TAB_4") (pintype "bidirectional"))
      (node (ref "U8") (pin "8") (pinfunction "VCC_8") (pintype "power_in"))
      (node (ref "U9") (pin "10") (pinfunction "VDDIO_10") (pintype "bidirectional"))
      (node (ref "VDD_3V3") (pin "P$1") (pinfunction "P$1_P$1") (pintype "passive"))
    )
    (net (code "101") (name "VDD_3V3_ANALOG") (class "Default")
      (node (ref "C13") (pin "A") (pinfunction "+_A") (pintype "passive"))
      (node (ref "C15") (pin "1") (pinfunction "1_1") (pintype "passive"))
      (node (ref "C18") (pin "1") (pinfunction "1_1") (pintype "passive"))
      (node (ref "C19") (pin "1") (pinfunction "1_1") (pintype "passive"))
      (node (ref "C21") (pin "1") (pinfunction "1_1") (pintype "passive"))
      (node (ref "C22") (pin "1") (pinfunction "1_1") (pintype "passive"))
      (node (ref "C28") (pin "1") (pinfunction "1_1") (pintype "passive"))
      (node (ref "U1") (pin "13") (pinfunction "VDDA_13") (pintype "power_in"))
      (node (ref "U10") (pin "1") (pinfunction "VDD_1") (pintype "bidirectional"))
      (node (ref "U10") (pin "2") (pinfunction "PS_2") (pintype "bidirectional"))
      (node (ref "U10") (pin "4") (pinfunction "CSB1_4") (pintype "bidirectional"))
      (node (ref "U10") (pin "5") (pinfunction "CSB2_5") (pintype "bidirectional"))
      (node (ref "U11") (pin "13") (pinfunction "VDDIO_13") (pintype "bidirectional"))
      (node (ref "U11") (pin "2") (pinfunction "VDD_2") (pintype "bidirectional"))
      (node (ref "U11") (pin "4") (pinfunction "S1_VDDIO_4") (pintype "bidirectional"))
      (node (ref "U12") (pin "15") (pinfunction "RES_P15_VDD_15") (pintype "bidirectional"))
      (node (ref "U12") (pin "16") (pinfunction "VDD_16") (pintype "bidirectional"))
      (node (ref "U14") (pin "13") (pinfunction "VDD_13") (pintype "bidirectional"))
      (node (ref "U7") (pin "5") (pinfunction "OUT_5") (pintype "passive"))
      (node (ref "U9") (pin "2") (pinfunction "VDD_2") (pintype "bidirectional"))
      (node (ref "VDDA_3V3") (pin "P$1") (pinfunction "P$1_P$1") (pintype "passive"))
    )
    (net (code "102") (name "VDD_5V") (class "Default")
      (node (ref "C27") (pin "A") (pinfunction "+_A") (pintype "passive"))
      (node (ref "C7") (pin "1") (pinfunction "1_1") (pintype "passive"))
      (node (ref "D2") (pin "2") (pinfunction "A2_2") (pintype "passive"))
      (node (ref "JP1") (pin "3") (pinfunction "3_3") (pintype "passive"))
      (node (ref "JP2") (pin "1") (pinfunction "1_1") (pintype "passive"))
      (node (ref "L1") (pin "1") (pinfunction "1_1") (pintype "passive"))
      (node (ref "L11") (pin "1") (pinfunction "1_1") (pintype "passive"))
      (node (ref "Q1") (pin "4") (pinfunction "S_4") (pintype "passive"))
      (node (ref "R1") (pin "2") (pinfunction "2_2") (pintype "passive"))
      (node (ref "R2") (pin "2") (pinfunction "2_2") (pintype "passive"))
      (node (ref "U6") (pin "3") (pinfunction "VIN_3") (pintype "bidirectional"))
    )
    (net (code "103") (name "VDD_5V_IN") (class "Default")
      (node (ref "D1") (pin "CATHODE") (pinfunction "C_CATHODE") (pintype "passive"))
      (node (ref "J2") (pin "1") (pinfunction "S_1") (pintype "passive"))
      (node (ref "J2") (pin "2") (pinfunction "S_2") (pintype "passive"))
      (node (ref "J3") (pin "1") (pinfunction "S_1") (pintype "passive"))
      (node (ref "J3") (pin "2") (pinfunction "S_2") (pintype "passive"))
      (node (ref "Q1") (pin "1") (pinfunction "D_1") (pintype "passive"))
      (node (ref "Q1") (pin "2") (pinfunction "D1_2") (pintype "passive"))
      (node (ref "Q1") (pin "5") (pinfunction "D2_5") (pintype "passive"))
      (node (ref "Q1") (pin "6") (pinfunction "D3_6") (pintype "passive"))
    )
    (net (code "104") (name "VDD_IO") (class "Default")
      (node (ref "C1") (pin "1") (pinfunction "1_1") (pintype "passive"))
      (node (ref "JP1") (pin "2") (pinfunction "2_2") (pintype "passive"))
      (node (ref "U2") (pin "7") (pinfunction "VCCB_7") (pintype "input"))
      (node (ref "U3") (pin "7") (pinfunction "VCCB_7") (pintype "input"))
      (node (ref "U5") (pin "8") (pinfunction "VCCB_8") (pintype "passive"))
    )
    (net (code "105") (name "unconnected-(J4D-S-Pad4)") (class "Default")
      (node (ref "J4") (pin "4") (pinfunction "S_4") (pintype "passive"))
    )
    (net (code "106") (name "unconnected-(J5-4-PadID)") (class "Default")
      (node (ref "J5") (pin "ID") (pinfunction "4_ID") (pintype "passive"))
    )
    (net (code "107") (name "unconnected-(U8-WP-Pad7)") (class "Default")
      (node (ref "U8") (pin "7") (pinfunction "WP_7") (pintype "bidirectional"))
    )
    (net (code "108") (name "unconnected-(U9-INT-Pad4)") (class "Default")
      (node (ref "U9") (pin "4") (pinfunction "INT_4") (pintype "bidirectional"))
    )
    (net (code "109") (name "unconnected-(U9-NC-Pad1)") (class "Default")
      (node (ref "U9") (pin "1") (pinfunction "NC_1") (pintype "bidirectional"))
    )
    (net (code "110") (name "unconnected-(U9-NC1-Pad6)") (class "Default")
      (node (ref "U9") (pin "6") (pinfunction "NC1_6") (pintype "bidirectional"))
    )
    (net (code "111") (name "unconnected-(U9-NC2-Pad11)") (class "Default")
      (node (ref "U9") (pin "11") (pinfunction "NC2_11") (pintype "bidirectional"))
    )
    (net (code "112") (name "unconnected-(U9-NC3-Pad12)") (class "Default")
      (node (ref "U9") (pin "12") (pinfunction "NC3_12") (pintype "bidirectional"))
    )
    (net (code "113") (name "unconnected-(U10-SDO-Pad6)") (class "Default")
      (node (ref "U10") (pin "6") (pinfunction "SDO_6") (pintype "bidirectional"))
    )
    (net (code "114") (name "unconnected-(U11-NC_P3-Pad3)") (class "Default")
      (node (ref "U11") (pin "3") (pinfunction "NC_P3_3") (pintype "no_connect"))
    )
    (net (code "115") (name "unconnected-(U11-NC_P5-Pad5)") (class "Default")
      (node (ref "U11") (pin "5") (pinfunction "NC_P5_5") (pintype "no_connect"))
    )
    (net (code "116") (name "unconnected-(U11-NC_P6-Pad6)") (class "Default")
      (node (ref "U11") (pin "6") (pinfunction "NC_P6_6") (pintype "no_connect"))
    )
    (net (code "117") (name "unconnected-(U11-NC_P7-Pad7)") (class "Default")
      (node (ref "U11") (pin "7") (pinfunction "NC_P7_7") (pintype "no_connect"))
    )
    (net (code "118") (name "unconnected-(U11-NC_P14-Pad14)") (class "Default")
      (node (ref "U11") (pin "14") (pinfunction "NC_P14_14") (pintype "no_connect"))
    )
    (net (code "119") (name "unconnected-(U12-DRDY{slash}INT2-Pad6)") (class "Default")
      (node (ref "U12") (pin "6") (pinfunction "DRDY/INT2_6") (pintype "output"))
    )
    (net (code "120") (name "unconnected-(U12-INT1-Pad7)") (class "Default")
      (node (ref "U12") (pin "7") (pinfunction "INT1_7") (pintype "output"))
    )
    (net (code "121") (name "unconnected-(U14-AUX_CL-Pad7)") (class "Default")
      (node (ref "U14") (pin "7") (pinfunction "AUX_CL_7") (pintype "bidirectional"))
    )
    (net (code "122") (name "unconnected-(U14-AUX_DA-Pad6)") (class "Default")
      (node (ref "U14") (pin "6") (pinfunction "AUX_DA_6") (pintype "bidirectional"))
    )
    (net (code "123") (name "unconnected-(U14-CLKOUT-Pad22)") (class "Default")
      (node (ref "U14") (pin "22") (pinfunction "CLKOUT_22") (pintype "bidirectional"))
    )
    (net (code "124") (name "unconnected-(U14-NC1-Pad2)") (class "Default")
      (node (ref "U14") (pin "2") (pinfunction "NC1_2") (pintype "bidirectional"))
    )
    (net (code "125") (name "unconnected-(U14-NC2-Pad3)") (class "Default")
      (node (ref "U14") (pin "3") (pinfunction "NC2_3") (pintype "bidirectional"))
    )
    (net (code "126") (name "unconnected-(U14-NC3-Pad4)") (class "Default")
      (node (ref "U14") (pin "4") (pinfunction "NC3_4") (pintype "bidirectional"))
    )
    (net (code "127") (name "unconnected-(U14-NC4-Pad5)") (class "Default")
      (node (ref "U14") (pin "5") (pinfunction "NC4_5") (pintype "bidirectional"))
    )
    (net (code "128") (name "unconnected-(U14-NC5-Pad14)") (class "Default")
      (node (ref "U14") (pin "14") (pinfunction "NC5_14") (pintype "bidirectional"))
    )
    (net (code "129") (name "unconnected-(U14-NC6-Pad15)") (class "Default")
      (node (ref "U14") (pin "15") (pinfunction "NC6_15") (pintype "bidirectional"))
    )
    (net (code "130") (name "unconnected-(U14-NC7-Pad16)") (class "Default")
      (node (ref "U14") (pin "16") (pinfunction "NC7_16") (pintype "bidirectional"))
    )
    (net (code "131") (name "unconnected-(U14-NC8-Pad17)") (class "Default")
      (node (ref "U14") (pin "17") (pinfunction "NC8_17") (pintype "bidirectional"))
    )
    (net (code "132") (name "unconnected-(U14-RESV1-Pad19)") (class "Default")
      (node (ref "U14") (pin "19") (pinfunction "RESV1_19") (pintype "bidirectional"))
    )
    (net (code "133") (name "unconnected-(U14-RESV2-Pad21)") (class "Default")
      (node (ref "U14") (pin "21") (pinfunction "RESV2_21") (pintype "bidirectional"))
    )
    (net (code "134") (name "~{JTRST}") (class "Default")
      (node (ref "!JTRST") (pin "P$1") (pinfunction "P$1_P$1") (pintype "passive"))
      (node (ref "J6") (pin "10") (pinfunction "S_10") (pintype "passive"))
      (node (ref "U1") (pin "56") (pinfunction "PB4_56") (pintype "bidirectional"))
    )
  )
)
